# llrf_afe_fpga_bridge.net
KiCad netlist of a schematic drawn in Altium Designer
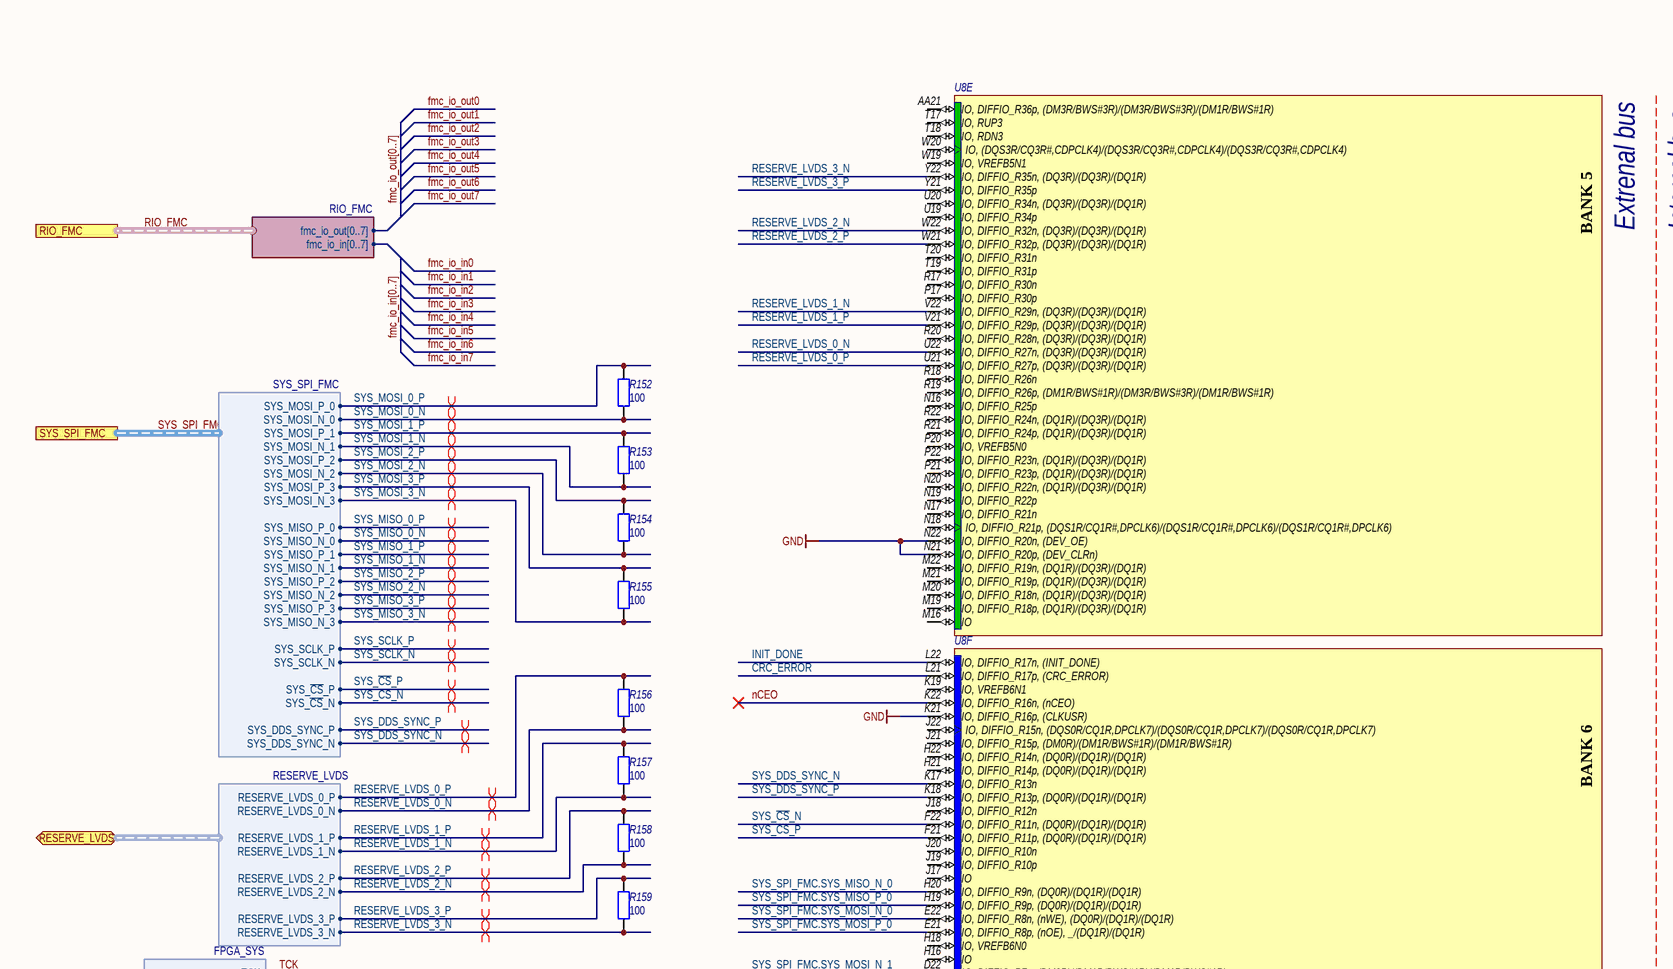
[diagram p0: llrf_afe_fpga_bridge.SchDoc, top left]
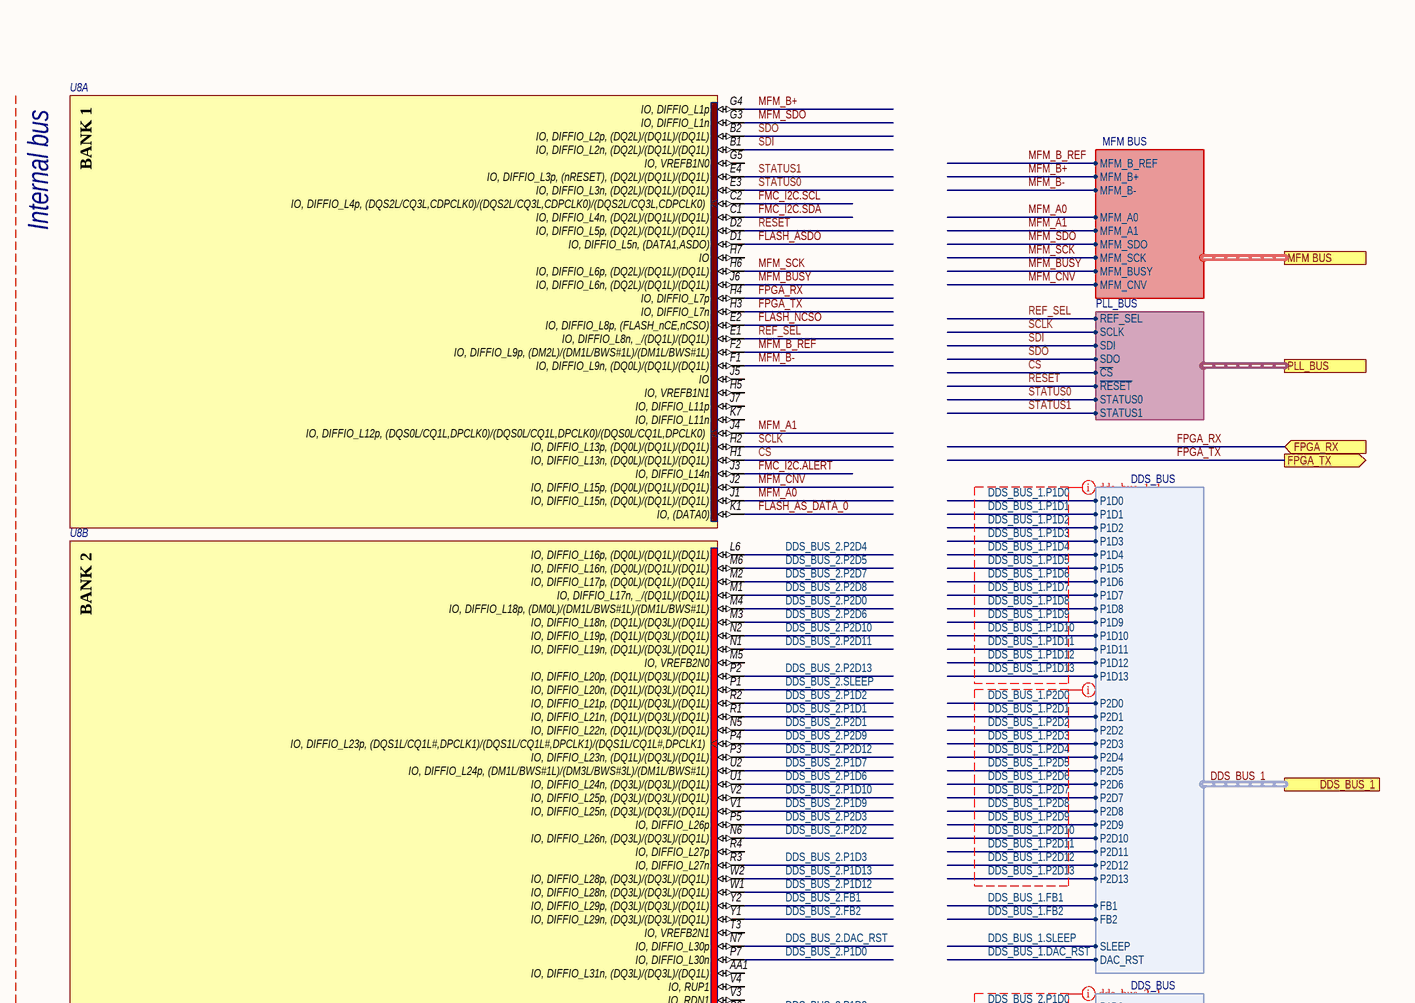
[diagram p1: llrf_afe_fpga_bridge.SchDoc, top right]
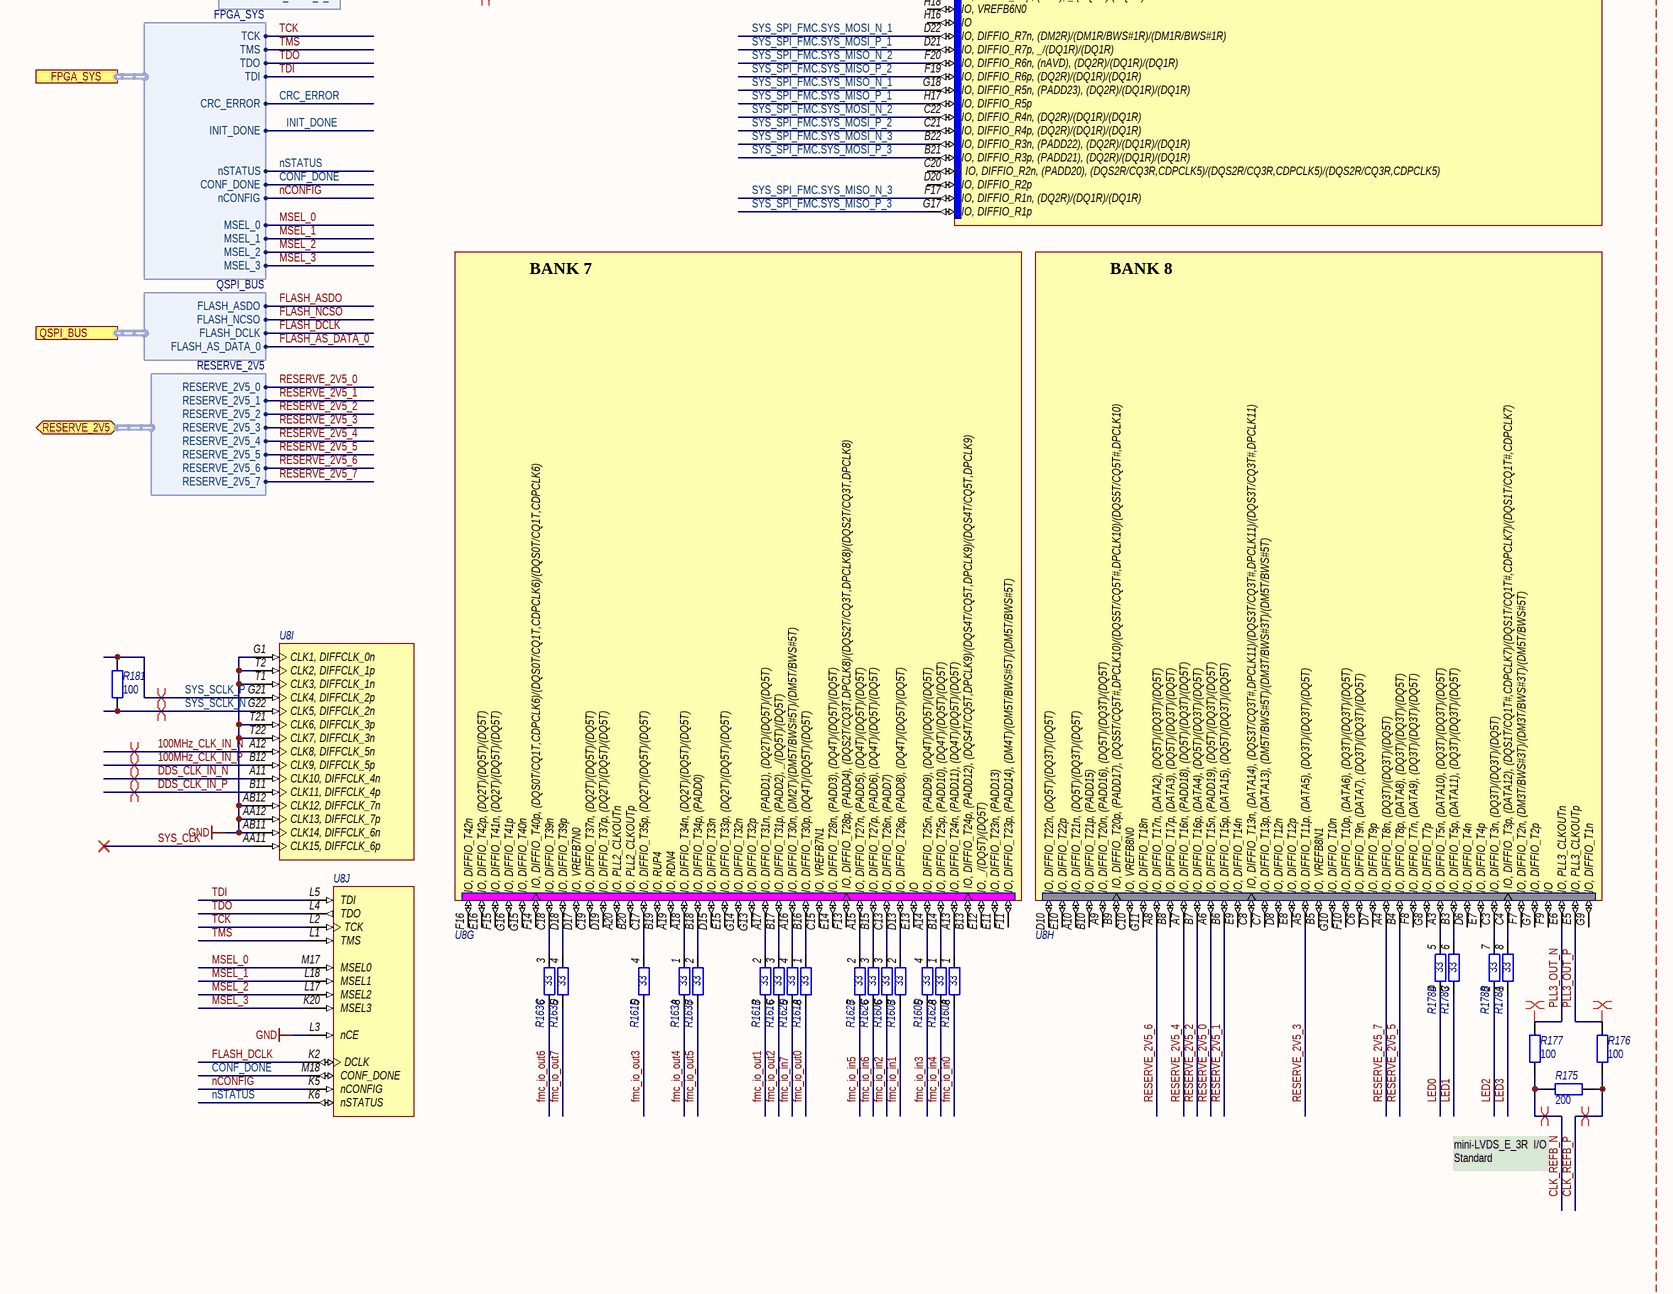
[diagram p2: llrf_afe_fpga_bridge.SchDoc, bottom left]
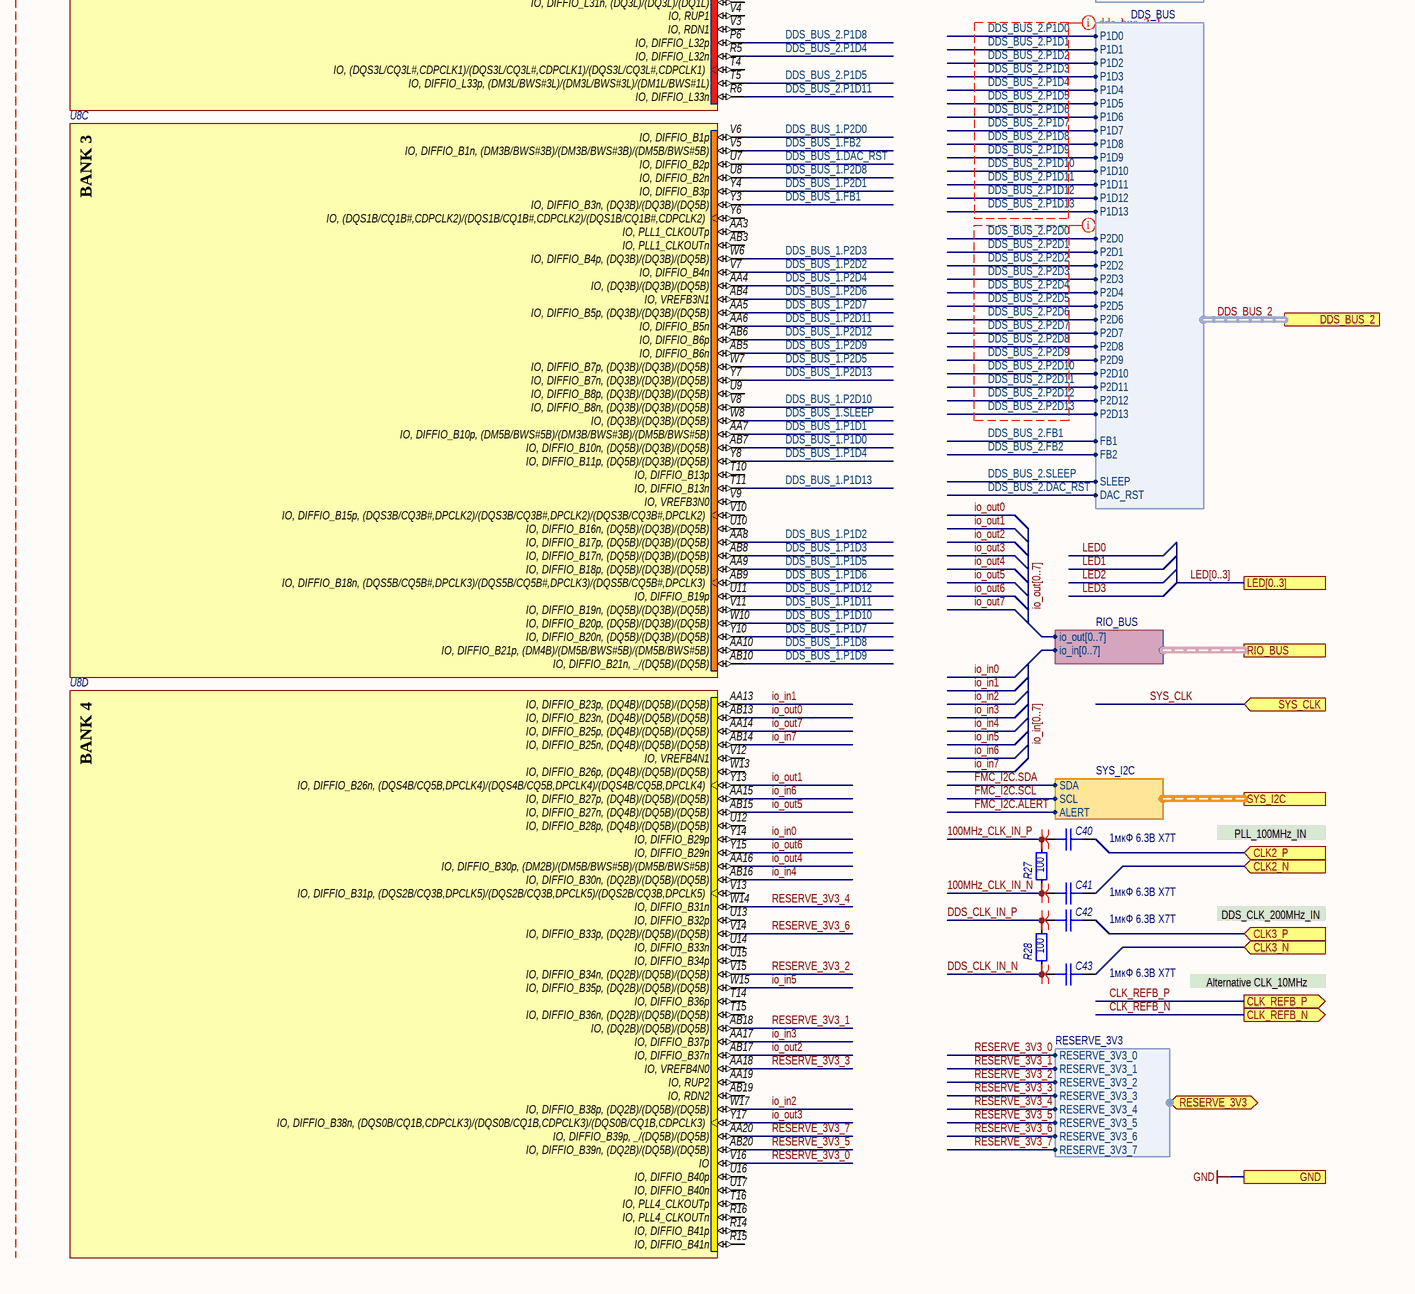
[diagram p3: llrf_afe_fpga_bridge.SchDoc, bottom right]

(export (version "E")
  (design (tool "Eeschema 10.0.6"))
  (components
    (comp (ref "C40")
      (value "1мкФ 6.3В X7T")
      (footprint "SMD_C0603")
      (description "Capacitor")
      (libsource (lib "Passive") (part "Capacitor"))
    )
    (comp (ref "C41")
      (value "1мкФ 6.3В X7T")
      (footprint "SMD_C0603")
      (description "Capacitor")
      (libsource (lib "Passive") (part "Capacitor"))
    )
    (comp (ref "C42")
      (value "1мкФ 6.3В X7T")
      (footprint "SMD_C0603")
      (description "Capacitor")
      (libsource (lib "Passive") (part "Capacitor"))
    )
    (comp (ref "C43")
      (value "1мкФ 6.3В X7T")
      (footprint "SMD_C0603")
      (description "Capacitor")
      (libsource (lib "Passive") (part "Capacitor"))
    )
    (comp (ref "R27")
      (value "100")
      (footprint "SMD_0603")
      (description "Resistor")
      (libsource (lib "") (part "Resistor_1"))
    )
    (comp (ref "R28")
      (value "100")
      (footprint "SMD_0603")
      (description "Resistor")
      (libsource (lib "") (part "Resistor_1"))
    )
    (comp (ref "R152")
      (value "100")
      (footprint "SMD_0603")
      (description "Resistor")
      (libsource (lib "Passive") (part "Resistor"))
    )
    (comp (ref "R153")
      (value "100")
      (footprint "SMD_0603")
      (description "Resistor")
      (libsource (lib "Passive") (part "Resistor"))
    )
    (comp (ref "R154")
      (value "100")
      (footprint "SMD_0603")
      (description "Resistor")
      (libsource (lib "Passive") (part "Resistor"))
    )
    (comp (ref "R155")
      (value "100")
      (footprint "SMD_0603")
      (description "Resistor")
      (libsource (lib "Passive") (part "Resistor"))
    )
    (comp (ref "R156")
      (value "100")
      (footprint "SMD_0603")
      (description "Resistor")
      (libsource (lib "Passive") (part "Resistor"))
    )
    (comp (ref "R157")
      (value "100")
      (footprint "SMD_0603")
      (description "Resistor")
      (libsource (lib "Passive") (part "Resistor"))
    )
    (comp (ref "R158")
      (value "100")
      (footprint "SMD_0603")
      (description "Resistor")
      (libsource (lib "Passive") (part "Resistor"))
    )
    (comp (ref "R159")
      (value "100")
      (footprint "SMD_0603")
      (description "Resistor")
      (libsource (lib "Passive") (part "Resistor"))
    )
    (comp (ref "R160")
      (value "33")
      (footprint "TC124")
      (description "4 Chip Resistor Array")
      (libsource (lib "") (part "Resistor-4_1"))
    )
    (comp (ref "R161")
      (value "33")
      (footprint "TC124")
      (description "4 Chip Resistor Array")
      (libsource (lib "") (part "Resistor-4_1"))
    )
    (comp (ref "R162")
      (value "33")
      (footprint "TC124")
      (description "4 Chip Resistor Array")
      (libsource (lib "") (part "Resistor-4_1"))
    )
    (comp (ref "R163")
      (value "33")
      (footprint "TC124")
      (description "4 Chip Resistor Array")
      (libsource (lib "") (part "Resistor-4_1"))
    )
    (comp (ref "R175")
      (value "200")
      (footprint "SMD_0603")
      (description "Resistor")
      (libsource (lib "") (part "Resistor_2"))
    )
    (comp (ref "R176")
      (value "100")
      (footprint "SMD_0603")
      (description "Resistor")
      (libsource (lib "Passive") (part "Resistor"))
    )
    (comp (ref "R177")
      (value "100")
      (footprint "SMD_0603")
      (description "Resistor")
      (libsource (lib "Passive") (part "Resistor"))
    )
    (comp (ref "R178")
      (value "33")
      (footprint "TC124")
      (description "4 Chip Resistor Array")
      (libsource (lib "Passive") (part "Resistor-4"))
    )
    (comp (ref "R181")
      (value "100")
      (footprint "SMD_0603")
      (description "Resistor")
      (libsource (lib "Passive") (part "Resistor"))
    )
    (comp (ref "U8")
      (value "EP4CE55F23C8")
      (footprint "FBGA484_A-240")
      (fields (field (name "MANUFACTURER") "Altera"))
      (libsource (lib "Altium Content Vault") (part "FPGA-ALEP4C-EP4CE55-F484"))
    )
  )
  (nets
    (net (code "15") (name "/100MHz_CLK_IN_N") (class "Default")
      (node (ref "C41") (pin "1") (pinfunction "1_1") (pintype "passive"))
      (node (ref "R27") (pin "1") (pinfunction "1_1") (pintype "passive"))
      (node (ref "U8") (pin "A12") (pinfunction "CLK8,_DIFFCLK_5n_A12") (pintype "input"))
    )
    (net (code "16") (name "/100MHz_CLK_IN_P") (class "Default")
      (node (ref "C40") (pin "2") (pinfunction "2_2") (pintype "passive"))
      (node (ref "R27") (pin "2") (pinfunction "2_2") (pintype "passive"))
      (node (ref "U8") (pin "B12") (pinfunction "CLK9,_DIFFCLK_5p_B12") (pintype "input"))
    )
    (net (code "17") (name "/CLK2_N") (class "Default")
      (node (ref "C41") (pin "2") (pinfunction "2_2") (pintype "passive"))
    )
    (net (code "18") (name "/CLK2_P") (class "Default")
      (node (ref "C40") (pin "1") (pinfunction "1_1") (pintype "passive"))
    )
    (net (code "19") (name "/CLK3_N") (class "Default")
      (node (ref "C43") (pin "2") (pinfunction "2_2") (pintype "passive"))
    )
    (net (code "20") (name "/CLK3_P") (class "Default")
      (node (ref "C42") (pin "1") (pinfunction "1_1") (pintype "passive"))
    )
    (net (code "21") (name "/CLK_REFB_N") (class "Default")
      (node (ref "R175") (pin "2") (pinfunction "2_2") (pintype "passive"))
      (node (ref "R177") (pin "2") (pinfunction "2_2") (pintype "passive"))
    )
    (net (code "22") (name "/CLK_REFB_P") (class "Default")
      (node (ref "R175") (pin "1") (pinfunction "1_1") (pintype "passive"))
      (node (ref "R176") (pin "2") (pinfunction "2_2") (pintype "passive"))
    )
    (net (code "23") (name "/CONF_DONE") (class "Default")
      (node (ref "U8") (pin "M18") (pinfunction "CONF_DONE_M18") (pintype "bidirectional"))
    )
    (net (code "24") (name "/CRC_ERROR") (class "Default")
      (node (ref "U8") (pin "L21") (pinfunction "IO,_DIFFIO_R17p,_(CRC_ERROR)_L21") (pintype "bidirectional"))
    )
    (net (code "25") (name "/DDS_BUS_1.DAC_RST") (class "Default")
      (node (ref "U8") (pin "U7") (pinfunction "IO,_DIFFIO_B2p_U7") (pintype "bidirectional"))
    )
    (net (code "26") (name "/DDS_BUS_1.FB1") (class "Default")
      (node (ref "U8") (pin "Y3") (pinfunction "IO,_DIFFIO_B3n,_(DQ3B)/(DQ3B)/(DQ5B)_Y3") (pintype "bidirectional"))
    )
    (net (code "27") (name "/DDS_BUS_1.FB2") (class "Default")
      (node (ref "U8") (pin "V5") (pinfunction "IO,_DIFFIO_B1n,_(DM3B/BWS#3B)/(DM3B/BWS#3B)/(DM5B/BWS#5B)_V5") (pintype "bidirectional"))
    )
    (net (code "28") (name "/DDS_BUS_1.P1D0") (class "Default")
      (node (ref "U8") (pin "AB7") (pinfunction "IO,_DIFFIO_B10n,_(DQ5B)/(DQ3B)/(DQ5B)_AB7") (pintype "bidirectional"))
    )
    (net (code "29") (name "/DDS_BUS_1.P1D1") (class "Default")
      (node (ref "U8") (pin "AA7") (pinfunction "IO,_DIFFIO_B10p,_(DM5B/BWS#5B)/(DM3B/BWS#3B)/(DM5B/BWS#5B)_AA7") (pintype "bidirectional"))
    )
    (net (code "30") (name "/DDS_BUS_1.P1D2") (class "Default")
      (node (ref "U8") (pin "AA8") (pinfunction "IO,_DIFFIO_B17p,_(DQ5B)/(DQ3B)/(DQ5B)_AA8") (pintype "bidirectional"))
    )
    (net (code "31") (name "/DDS_BUS_1.P1D3") (class "Default")
      (node (ref "U8") (pin "AB8") (pinfunction "IO,_DIFFIO_B17n,_(DQ5B)/(DQ3B)/(DQ5B)_AB8") (pintype "bidirectional"))
    )
    (net (code "32") (name "/DDS_BUS_1.P1D4") (class "Default")
      (node (ref "U8") (pin "Y8") (pinfunction "IO,_DIFFIO_B11p,_(DQ5B)/(DQ3B)/(DQ5B)_Y8") (pintype "bidirectional"))
    )
    (net (code "33") (name "/DDS_BUS_1.P1D5") (class "Default")
      (node (ref "U8") (pin "AA9") (pinfunction "IO,_DIFFIO_B18p,_(DQ5B)/(DQ3B)/(DQ5B)_AA9") (pintype "bidirectional"))
    )
    (net (code "34") (name "/DDS_BUS_1.P1D6") (class "Default")
      (node (ref "U8") (pin "AB9") (pinfunction "IO,_DIFFIO_B18n,_(DQS5B/CQ5B#,DPCLK3)/(DQS5B/CQ5B#,DPCLK3)/(DQS5B/CQ5B#,DPCLK3)_AB9") (pintype "bidirectional"))
    )
    (net (code "35") (name "/DDS_BUS_1.P1D7") (class "Default")
      (node (ref "U8") (pin "Y10") (pinfunction "IO,_DIFFIO_B20n,_(DQ5B)/(DQ3B)/(DQ5B)_Y10") (pintype "bidirectional"))
    )
    (net (code "36") (name "/DDS_BUS_1.P1D8") (class "Default")
      (node (ref "U8") (pin "AA10") (pinfunction "IO,_DIFFIO_B21p,_(DM4B)/(DM5B/BWS#5B)/(DM5B/BWS#5B)_AA10") (pintype "bidirectional"))
    )
    (net (code "37") (name "/DDS_BUS_1.P1D9") (class "Default")
      (node (ref "U8") (pin "AB10") (pinfunction "IO,_DIFFIO_B21n,__/(DQ5B)/(DQ5B)_AB10") (pintype "bidirectional"))
    )
    (net (code "38") (name "/DDS_BUS_1.P1D10") (class "Default")
      (node (ref "U8") (pin "W10") (pinfunction "IO,_DIFFIO_B20p,_(DQ5B)/(DQ3B)/(DQ5B)_W10") (pintype "bidirectional"))
    )
    (net (code "39") (name "/DDS_BUS_1.P1D11") (class "Default")
      (node (ref "U8") (pin "V11") (pinfunction "IO,_DIFFIO_B19n,_(DQ5B)/(DQ3B)/(DQ5B)_V11") (pintype "bidirectional"))
    )
    (net (code "40") (name "/DDS_BUS_1.P1D12") (class "Default")
      (node (ref "U8") (pin "U11") (pinfunction "IO,_DIFFIO_B19p_U11") (pintype "bidirectional"))
    )
    (net (code "41") (name "/DDS_BUS_1.P1D13") (class "Default")
      (node (ref "U8") (pin "T11") (pinfunction "IO,_DIFFIO_B13n_T11") (pintype "bidirectional"))
    )
    (net (code "42") (name "/DDS_BUS_1.P2D0") (class "Default")
      (node (ref "U8") (pin "V6") (pinfunction "IO,_DIFFIO_B1p_V6") (pintype "bidirectional"))
    )
    (net (code "43") (name "/DDS_BUS_1.P2D1") (class "Default")
      (node (ref "U8") (pin "Y4") (pinfunction "IO,_DIFFIO_B3p_Y4") (pintype "bidirectional"))
    )
    (net (code "44") (name "/DDS_BUS_1.P2D2") (class "Default")
      (node (ref "U8") (pin "V7") (pinfunction "IO,_DIFFIO_B4n_V7") (pintype "bidirectional"))
    )
    (net (code "45") (name "/DDS_BUS_1.P2D3") (class "Default")
      (node (ref "U8") (pin "W6") (pinfunction "IO,_DIFFIO_B4p,_(DQ3B)/(DQ3B)/(DQ5B)_W6") (pintype "bidirectional"))
    )
    (net (code "46") (name "/DDS_BUS_1.P2D4") (class "Default")
      (node (ref "U8") (pin "AA4") (pinfunction "IO,_(DQ3B)/(DQ3B)/(DQ5B)_AA4") (pintype "bidirectional"))
    )
    (net (code "47") (name "/DDS_BUS_1.P2D5") (class "Default")
      (node (ref "U8") (pin "W7") (pinfunction "IO,_DIFFIO_B7p,_(DQ3B)/(DQ3B)/(DQ5B)_W7") (pintype "bidirectional"))
    )
    (net (code "48") (name "/DDS_BUS_1.P2D6") (class "Default")
      (node (ref "U8") (pin "AB4") (pinfunction "IO,_VREFB3N1_AB4") (pintype "bidirectional"))
    )
    (net (code "49") (name "/DDS_BUS_1.P2D7") (class "Default")
      (node (ref "U8") (pin "AA5") (pinfunction "IO,_DIFFIO_B5p,_(DQ3B)/(DQ3B)/(DQ5B)_AA5") (pintype "bidirectional"))
    )
    (net (code "50") (name "/DDS_BUS_1.P2D8") (class "Default")
      (node (ref "U8") (pin "U8") (pinfunction "IO,_DIFFIO_B2n_U8") (pintype "bidirectional"))
    )
    (net (code "51") (name "/DDS_BUS_1.P2D9") (class "Default")
      (node (ref "U8") (pin "AB5") (pinfunction "IO,_DIFFIO_B6n_AB5") (pintype "bidirectional"))
    )
    (net (code "52") (name "/DDS_BUS_1.P2D10") (class "Default")
      (node (ref "U8") (pin "V8") (pinfunction "IO,_DIFFIO_B8n,_(DQ3B)/(DQ3B)/(DQ5B)_V8") (pintype "bidirectional"))
    )
    (net (code "53") (name "/DDS_BUS_1.P2D11") (class "Default")
      (node (ref "U8") (pin "AA6") (pinfunction "IO,_DIFFIO_B5n_AA6") (pintype "bidirectional"))
    )
    (net (code "54") (name "/DDS_BUS_1.P2D12") (class "Default")
      (node (ref "U8") (pin "AB6") (pinfunction "IO,_DIFFIO_B6p_AB6") (pintype "bidirectional"))
    )
    (net (code "55") (name "/DDS_BUS_1.P2D13") (class "Default")
      (node (ref "U8") (pin "Y7") (pinfunction "IO,_DIFFIO_B7n,_(DQ3B)/(DQ3B)/(DQ5B)_Y7") (pintype "bidirectional"))
    )
    (net (code "56") (name "/DDS_BUS_1.SLEEP") (class "Default")
      (node (ref "U8") (pin "W8") (pinfunction "IO,_(DQ3B)/(DQ3B)/(DQ5B)_W8") (pintype "bidirectional"))
    )
    (net (code "58") (name "/DDS_BUS_2.DAC_RST") (class "Default")
      (node (ref "U8") (pin "N7") (pinfunction "IO,_DIFFIO_L30p_N7") (pintype "bidirectional"))
    )
    (net (code "59") (name "/DDS_BUS_2.FB1") (class "Default")
      (node (ref "U8") (pin "Y2") (pinfunction "IO,_DIFFIO_L29p,_(DQ3L)/(DQ3L)/(DQ1L)_Y2") (pintype "bidirectional"))
    )
    (net (code "60") (name "/DDS_BUS_2.FB2") (class "Default")
      (node (ref "U8") (pin "Y1") (pinfunction "IO,_DIFFIO_L29n,_(DQ3L)/(DQ3L)/(DQ1L)_Y1") (pintype "bidirectional"))
    )
    (net (code "61") (name "/DDS_BUS_2.P1D0") (class "Default")
      (node (ref "U8") (pin "P7") (pinfunction "IO,_DIFFIO_L30n_P7") (pintype "bidirectional"))
    )
    (net (code "62") (name "/DDS_BUS_2.P1D1") (class "Default")
      (node (ref "U8") (pin "R1") (pinfunction "IO,_DIFFIO_L21n,_(DQ1L)/(DQ3L)/(DQ1L)_R1") (pintype "bidirectional"))
    )
    (net (code "63") (name "/DDS_BUS_2.P1D2") (class "Default")
      (node (ref "U8") (pin "R2") (pinfunction "IO,_DIFFIO_L21p,_(DQ1L)/(DQ3L)/(DQ1L)_R2") (pintype "bidirectional"))
    )
    (net (code "64") (name "/DDS_BUS_2.P1D3") (class "Default")
      (node (ref "U8") (pin "R3") (pinfunction "IO,_DIFFIO_L27n_R3") (pintype "bidirectional"))
    )
    (net (code "65") (name "/DDS_BUS_2.P1D4") (class "Default")
      (node (ref "U8") (pin "R5") (pinfunction "IO,_DIFFIO_L32n_R5") (pintype "bidirectional"))
    )
    (net (code "66") (name "/DDS_BUS_2.P1D5") (class "Default")
      (node (ref "U8") (pin "T5") (pinfunction "IO,_DIFFIO_L33p,_(DM3L/BWS#3L)/(DM3L/BWS#3L)/(DM1L/BWS#1L)_T5") (pintype "bidirectional"))
    )
    (net (code "67") (name "/DDS_BUS_2.P1D6") (class "Default")
      (node (ref "U8") (pin "U1") (pinfunction "IO,_DIFFIO_L24n,_(DQ3L)/(DQ3L)/(DQ1L)_U1") (pintype "bidirectional"))
    )
    (net (code "68") (name "/DDS_BUS_2.P1D7") (class "Default")
      (node (ref "U8") (pin "U2") (pinfunction "IO,_DIFFIO_L24p,_(DM1L/BWS#1L)/(DM3L/BWS#3L)/(DM1L/BWS#1L)_U2") (pintype "bidirectional"))
    )
    (net (code "69") (name "/DDS_BUS_2.P1D8") (class "Default")
      (node (ref "U8") (pin "P6") (pinfunction "IO,_DIFFIO_L32p_P6") (pintype "bidirectional"))
    )
    (net (code "70") (name "/DDS_BUS_2.P1D9") (class "Default")
      (node (ref "U8") (pin "V1") (pinfunction "IO,_DIFFIO_L25n,_(DQ3L)/(DQ3L)/(DQ1L)_V1") (pintype "bidirectional"))
    )
    (net (code "71") (name "/DDS_BUS_2.P1D10") (class "Default")
      (node (ref "U8") (pin "V2") (pinfunction "IO,_DIFFIO_L25p,_(DQ3L)/(DQ3L)/(DQ1L)_V2") (pintype "bidirectional"))
    )
    (net (code "72") (name "/DDS_BUS_2.P1D11") (class "Default")
      (node (ref "U8") (pin "R6") (pinfunction "IO,_DIFFIO_L33n_R6") (pintype "bidirectional"))
    )
    (net (code "73") (name "/DDS_BUS_2.P1D12") (class "Default")
      (node (ref "U8") (pin "W1") (pinfunction "IO,_DIFFIO_L28n,_(DQ3L)/(DQ3L)/(DQ1L)_W1") (pintype "bidirectional"))
    )
    (net (code "74") (name "/DDS_BUS_2.P1D13") (class "Default")
      (node (ref "U8") (pin "W2") (pinfunction "IO,_DIFFIO_L28p,_(DQ3L)/(DQ3L)/(DQ1L)_W2") (pintype "bidirectional"))
    )
    (net (code "75") (name "/DDS_BUS_2.P2D0") (class "Default")
      (node (ref "U8") (pin "M4") (pinfunction "IO,_DIFFIO_L18p,_(DM0L)/(DM1L/BWS#1L)/(DM1L/BWS#1L)_M4") (pintype "bidirectional"))
    )
    (net (code "76") (name "/DDS_BUS_2.P2D1") (class "Default")
      (node (ref "U8") (pin "N5") (pinfunction "IO,_DIFFIO_L22n,_(DQ1L)/(DQ3L)/(DQ1L)_N5") (pintype "bidirectional"))
    )
    (net (code "77") (name "/DDS_BUS_2.P2D2") (class "Default")
      (node (ref "U8") (pin "N6") (pinfunction "IO,_DIFFIO_L26n,_(DQ3L)/(DQ3L)/(DQ1L)_N6") (pintype "bidirectional"))
    )
    (net (code "78") (name "/DDS_BUS_2.P2D3") (class "Default")
      (node (ref "U8") (pin "P5") (pinfunction "IO,_DIFFIO_L26p_P5") (pintype "bidirectional"))
    )
    (net (code "79") (name "/DDS_BUS_2.P2D4") (class "Default")
      (node (ref "U8") (pin "L6") (pinfunction "IO,_DIFFIO_L16p,_(DQ0L)/(DQ1L)/(DQ1L)_L6") (pintype "bidirectional"))
    )
    (net (code "80") (name "/DDS_BUS_2.P2D5") (class "Default")
      (node (ref "U8") (pin "M6") (pinfunction "IO,_DIFFIO_L16n,_(DQ0L)/(DQ1L)/(DQ1L)_M6") (pintype "bidirectional"))
    )
    (net (code "81") (name "/DDS_BUS_2.P2D6") (class "Default")
      (node (ref "U8") (pin "M3") (pinfunction "IO,_DIFFIO_L18n,_(DQ1L)/(DQ3L)/(DQ1L)_M3") (pintype "bidirectional"))
    )
    (net (code "82") (name "/DDS_BUS_2.P2D7") (class "Default")
      (node (ref "U8") (pin "M2") (pinfunction "IO,_DIFFIO_L17p,_(DQ0L)/(DQ1L)/(DQ1L)_M2") (pintype "bidirectional"))
    )
    (net (code "83") (name "/DDS_BUS_2.P2D8") (class "Default")
      (node (ref "U8") (pin "M1") (pinfunction "IO,_DIFFIO_L17n,__/(DQ1L)/(DQ1L)_M1") (pintype "bidirectional"))
    )
    (net (code "84") (name "/DDS_BUS_2.P2D9") (class "Default")
      (node (ref "U8") (pin "P4") (pinfunction "IO,_DIFFIO_L23p,_(DQS1L/CQ1L#,DPCLK1)/(DQS1L/CQ1L#,DPCLK1)/(DQS1L/CQ1L#,DPCLK1)_P4") (pintype "bidirectional"))
    )
    (net (code "85") (name "/DDS_BUS_2.P2D10") (class "Default")
      (node (ref "U8") (pin "N2") (pinfunction "IO,_DIFFIO_L19p,_(DQ1L)/(DQ3L)/(DQ1L)_N2") (pintype "bidirectional"))
    )
    (net (code "86") (name "/DDS_BUS_2.P2D11") (class "Default")
      (node (ref "U8") (pin "N1") (pinfunction "IO,_DIFFIO_L19n,_(DQ1L)/(DQ3L)/(DQ1L)_N1") (pintype "bidirectional"))
    )
    (net (code "87") (name "/DDS_BUS_2.P2D12") (class "Default")
      (node (ref "U8") (pin "P3") (pinfunction "IO,_DIFFIO_L23n,_(DQ1L)/(DQ3L)/(DQ1L)_P3") (pintype "bidirectional"))
    )
    (net (code "88") (name "/DDS_BUS_2.P2D13") (class "Default")
      (node (ref "U8") (pin "P2") (pinfunction "IO,_DIFFIO_L20p,_(DQ1L)/(DQ3L)/(DQ1L)_P2") (pintype "bidirectional"))
    )
    (net (code "89") (name "/DDS_BUS_2.SLEEP") (class "Default")
      (node (ref "U8") (pin "P1") (pinfunction "IO,_DIFFIO_L20n,_(DQ1L)/(DQ3L)/(DQ1L)_P1") (pintype "bidirectional"))
    )
    (net (code "91") (name "/DDS_CLK_IN_N") (class "Default")
      (node (ref "C43") (pin "1") (pinfunction "1_1") (pintype "passive"))
      (node (ref "R28") (pin "1") (pinfunction "1_1") (pintype "passive"))
      (node (ref "U8") (pin "A11") (pinfunction "CLK10,_DIFFCLK_4n_A11") (pintype "input"))
    )
    (net (code "92") (name "/DDS_CLK_IN_P") (class "Default")
      (node (ref "C42") (pin "2") (pinfunction "2_2") (pintype "passive"))
      (node (ref "R28") (pin "2") (pinfunction "2_2") (pintype "passive"))
      (node (ref "U8") (pin "B11") (pinfunction "CLK11,_DIFFCLK_4p_B11") (pintype "input"))
    )
    (net (code "93") (name "/FLASH_ASDO") (class "Default")
      (node (ref "U8") (pin "D1") (pinfunction "IO,_DIFFIO_L5n,_(DATA1,ASDO)_D1") (pintype "bidirectional"))
    )
    (net (code "94") (name "/FLASH_AS_DATA_0") (class "Default")
      (node (ref "U8") (pin "K1") (pinfunction "IO,_(DATA0)_K1") (pintype "bidirectional"))
    )
    (net (code "95") (name "/FLASH_DCLK") (class "Default")
      (node (ref "U8") (pin "K2") (pinfunction "DCLK_K2") (pintype "bidirectional"))
    )
    (net (code "96") (name "/FLASH_NCSO") (class "Default")
      (node (ref "U8") (pin "E2") (pinfunction "IO,_DIFFIO_L8p,_(FLASH_nCE,nCSO)_E2") (pintype "bidirectional"))
    )
    (net (code "97") (name "/FMC_I2C.ALERT") (class "Default")
      (node (ref "U8") (pin "J3") (pinfunction "IO,_DIFFIO_L14n_J3") (pintype "bidirectional"))
    )
    (net (code "98") (name "/FMC_I2C.SCL") (class "Default")
      (node (ref "U8") (pin "C2") (pinfunction "IO,_DIFFIO_L4p,_(DQS2L/CQ3L,CDPCLK0)/(DQS2L/CQ3L,CDPCLK0)/(DQS2L/CQ3L,CDPCLK0)_C2") (pintype "bidirectional"))
    )
    (net (code "99") (name "/FMC_I2C.SDA") (class "Default")
      (node (ref "U8") (pin "C1") (pinfunction "IO,_DIFFIO_L4n,_(DQ2L)/(DQ1L)/(DQ1L)_C1") (pintype "bidirectional"))
    )
    (net (code "100") (name "/FPGA_RX") (class "Default")
      (node (ref "U8") (pin "H4") (pinfunction "IO,_DIFFIO_L7p_H4") (pintype "bidirectional"))
    )
    (net (code "101") (name "/FPGA_TX") (class "Default")
      (node (ref "U8") (pin "H3") (pinfunction "IO,_DIFFIO_L7n_H3") (pintype "bidirectional"))
    )
    (net (code "102") (name "/INIT_DONE") (class "Default")
      (node (ref "U8") (pin "L22") (pinfunction "IO,_DIFFIO_R17n,_(INIT_DONE)_L22") (pintype "bidirectional"))
    )
    (net (code "103") (name "/LED0") (class "Default")
      (node (ref "R178") (pin "4") (pinfunction "4_4") (pintype "passive"))
    )
    (net (code "104") (name "/LED1") (class "Default")
      (node (ref "R178") (pin "3") (pinfunction "3_3") (pintype "passive"))
    )
    (net (code "105") (name "/LED2") (class "Default")
      (node (ref "R178") (pin "2") (pinfunction "2_2") (pintype "passive"))
    )
    (net (code "106") (name "/LED3") (class "Default")
      (node (ref "R178") (pin "1") (pinfunction "1_1") (pintype "passive"))
    )
    (net (code "108") (name "/MFM_A0") (class "Default")
      (node (ref "U8") (pin "J1") (pinfunction "IO,_DIFFIO_L15n,_(DQ0L)/(DQ1L)/(DQ1L)_J1") (pintype "bidirectional"))
    )
    (net (code "109") (name "/MFM_A1") (class "Default")
      (node (ref "U8") (pin "J4") (pinfunction "IO,_DIFFIO_L12p,_(DQS0L/CQ1L,DPCLK0)/(DQS0L/CQ1L,DPCLK0)/(DQS0L/CQ1L,DPCLK0)_J4") (pintype "bidirectional"))
    )
    (net (code "110") (name "/MFM_B+") (class "Default")
      (node (ref "U8") (pin "G4") (pinfunction "IO,_DIFFIO_L1p_G4") (pintype "bidirectional"))
    )
    (net (code "111") (name "/MFM_B-") (class "Default")
      (node (ref "U8") (pin "F1") (pinfunction "IO,_DIFFIO_L9n,_(DQ0L)/(DQ1L)/(DQ1L)_F1") (pintype "bidirectional"))
    )
    (net (code "112") (name "/MFM_BUSY") (class "Default")
      (node (ref "U8") (pin "J6") (pinfunction "IO,_DIFFIO_L6n,_(DQ2L)/(DQ1L)/(DQ1L)_J6") (pintype "bidirectional"))
    )
    (net (code "113") (name "/MFM_B_REF") (class "Default")
      (node (ref "U8") (pin "F2") (pinfunction "IO,_DIFFIO_L9p,_(DM2L)/(DM1L/BWS#1L)/(DM1L/BWS#1L)_F2") (pintype "bidirectional"))
    )
    (net (code "114") (name "/MFM_CNV") (class "Default")
      (node (ref "U8") (pin "J2") (pinfunction "IO,_DIFFIO_L15p,_(DQ0L)/(DQ1L)/(DQ1L)_J2") (pintype "bidirectional"))
    )
    (net (code "115") (name "/MFM_SCK") (class "Default")
      (node (ref "U8") (pin "H6") (pinfunction "IO,_DIFFIO_L6p,_(DQ2L)/(DQ1L)/(DQ1L)_H6") (pintype "bidirectional"))
    )
    (net (code "116") (name "/MFM_SDO") (class "Default")
      (node (ref "U8") (pin "G3") (pinfunction "IO,_DIFFIO_L1n_G3") (pintype "bidirectional"))
    )
    (net (code "117") (name "/MSEL_0") (class "Default")
      (node (ref "U8") (pin "M17") (pinfunction "MSEL0_M17") (pintype "input"))
    )
    (net (code "118") (name "/MSEL_1") (class "Default")
      (node (ref "U8") (pin "L18") (pinfunction "MSEL1_L18") (pintype "input"))
    )
    (net (code "119") (name "/MSEL_2") (class "Default")
      (node (ref "U8") (pin "L17") (pinfunction "MSEL2_L17") (pintype "input"))
    )
    (net (code "120") (name "/MSEL_3") (class "Default")
      (node (ref "U8") (pin "K20") (pinfunction "MSEL3_K20") (pintype "input"))
    )
    (net (code "121") (name "/PLL3_OUT_N") (class "Default")
      (node (ref "R177") (pin "1") (pinfunction "1_1") (pintype "passive"))
      (node (ref "U8") (pin "E6") (pinfunction "IO,_PLL3_CLKOUTn_E6") (pintype "bidirectional"))
    )
    (net (code "122") (name "/PLL3_OUT_P") (class "Default")
      (node (ref "R176") (pin "1") (pinfunction "1_1") (pintype "passive"))
      (node (ref "U8") (pin "E5") (pinfunction "IO,_PLL3_CLKOUTp_E5") (pintype "bidirectional"))
    )
    (net (code "123") (name "/REF_SEL") (class "Default")
      (node (ref "U8") (pin "E1") (pinfunction "IO,_DIFFIO_L8n,__/(DQ1L)/(DQ1L)_E1") (pintype "bidirectional"))
    )
    (net (code "124") (name "/RESERVE_2V5_0") (class "Default")
      (node (ref "U8") (pin "A6") (pinfunction "IO,_DIFFIO_T15n,_(PADD19),_(DQ5T)/(DQ3T)/(DQ5T)_A6") (pintype "bidirectional"))
    )
    (net (code "125") (name "/RESERVE_2V5_1") (class "Default")
      (node (ref "U8") (pin "B6") (pinfunction "IO,_DIFFIO_T15p,_(DATA15),_(DQ5T)/(DQ3T)/(DQ5T)_B6") (pintype "bidirectional"))
    )
    (net (code "126") (name "/RESERVE_2V5_2") (class "Default")
      (node (ref "U8") (pin "B7") (pinfunction "IO,_DIFFIO_T16p,_(DATA4),_(DQ5T)/(DQ3T)/(DQ5T)_B7") (pintype "bidirectional"))
    )
    (net (code "127") (name "/RESERVE_2V5_3") (class "Default")
      (node (ref "U8") (pin "A5") (pinfunction "IO,_DIFFIO_T11p,_(DATA5),_(DQ3T)/(DQ3T)/(DQ5T)_A5") (pintype "bidirectional"))
    )
    (net (code "128") (name "/RESERVE_2V5_4") (class "Default")
      (node (ref "U8") (pin "A7") (pinfunction "IO,_DIFFIO_T16n,_(PADD18),_(DQ5T)/(DQ3T)/(DQ5T)_A7") (pintype "bidirectional"))
    )
    (net (code "129") (name "/RESERVE_2V5_5") (class "Default")
      (node (ref "U8") (pin "B4") (pinfunction "IO,_DIFFIO_T8p,_(DATA8),_(DQ3T)/(DQ3T)/(DQ5T)_B4") (pintype "bidirectional"))
    )
    (net (code "130") (name "/RESERVE_2V5_6") (class "Default")
      (node (ref "U8") (pin "A8") (pinfunction "IO,_DIFFIO_T17n,_(DATA2),_(DQ5T)/(DQ3T)/(DQ5T)_A8") (pintype "bidirectional"))
    )
    (net (code "131") (name "/RESERVE_2V5_7") (class "Default")
      (node (ref "U8") (pin "A4") (pinfunction "IO,_DIFFIO_T8n,_(DQ3T)/(DQ3T)/(DQ5T)_A4") (pintype "bidirectional"))
    )
    (net (code "132") (name "/RESERVE_3V3_0") (class "Default")
      (node (ref "U8") (pin "V16") (pinfunction "IO_V16") (pintype "bidirectional"))
    )
    (net (code "133") (name "/RESERVE_3V3_1") (class "Default")
      (node (ref "U8") (pin "AB18") (pinfunction "IO,_(DQ2B)/(DQ5B)/(DQ5B)_AB18") (pintype "bidirectional"))
    )
    (net (code "134") (name "/RESERVE_3V3_2") (class "Default")
      (node (ref "U8") (pin "V15") (pinfunction "IO,_DIFFIO_B34n,_(DQ2B)/(DQ5B)/(DQ5B)_V15") (pintype "bidirectional"))
    )
    (net (code "135") (name "/RESERVE_3V3_3") (class "Default")
      (node (ref "U8") (pin "AA18") (pinfunction "IO,_VREFB4N0_AA18") (pintype "bidirectional"))
    )
    (net (code "136") (name "/RESERVE_3V3_4") (class "Default")
      (node (ref "U8") (pin "W14") (pinfunction "IO,_DIFFIO_B31n_W14") (pintype "bidirectional"))
    )
    (net (code "137") (name "/RESERVE_3V3_5") (class "Default")
      (node (ref "U8") (pin "AB20") (pinfunction "IO,_DIFFIO_B39n,_(DQ2B)/(DQ5B)/(DQ5B)_AB20") (pintype "bidirectional"))
    )
    (net (code "138") (name "/RESERVE_3V3_6") (class "Default")
      (node (ref "U8") (pin "V14") (pinfunction "IO,_DIFFIO_B33p,_(DQ2B)/(DQ5B)/(DQ5B)_V14") (pintype "bidirectional"))
    )
    (net (code "139") (name "/RESERVE_3V3_7") (class "Default")
      (node (ref "U8") (pin "AA20") (pinfunction "IO,_DIFFIO_B39p,__/(DQ5B)/(DQ5B)_AA20") (pintype "bidirectional"))
    )
    (net (code "140") (name "/RESERVE_LVDS_0_N") (class "Default")
      (node (ref "R156") (pin "2") (pinfunction "2_2") (pintype "passive"))
      (node (ref "U8") (pin "U22") (pinfunction "IO,_DIFFIO_R27n,_(DQ3R)/(DQ3R)/(DQ1R)_U22") (pintype "bidirectional"))
    )
    (net (code "141") (name "/RESERVE_LVDS_0_P") (class "Default")
      (node (ref "R156") (pin "1") (pinfunction "1_1") (pintype "passive"))
      (node (ref "U8") (pin "U21") (pinfunction "IO,_DIFFIO_R27p,_(DQ3R)/(DQ3R)/(DQ1R)_U21") (pintype "bidirectional"))
    )
    (net (code "142") (name "/RESERVE_LVDS_1_N") (class "Default")
      (node (ref "R157") (pin "2") (pinfunction "2_2") (pintype "passive"))
      (node (ref "U8") (pin "V22") (pinfunction "IO,_DIFFIO_R29n,_(DQ3R)/(DQ3R)/(DQ1R)_V22") (pintype "bidirectional"))
    )
    (net (code "143") (name "/RESERVE_LVDS_1_P") (class "Default")
      (node (ref "R157") (pin "1") (pinfunction "1_1") (pintype "passive"))
      (node (ref "U8") (pin "V21") (pinfunction "IO,_DIFFIO_R29p,_(DQ3R)/(DQ3R)/(DQ1R)_V21") (pintype "bidirectional"))
    )
    (net (code "144") (name "/RESERVE_LVDS_2_N") (class "Default")
      (node (ref "R158") (pin "2") (pinfunction "2_2") (pintype "passive"))
      (node (ref "U8") (pin "W22") (pinfunction "IO,_DIFFIO_R32n,_(DQ3R)/(DQ3R)/(DQ1R)_W22") (pintype "bidirectional"))
    )
    (net (code "145") (name "/RESERVE_LVDS_2_P") (class "Default")
      (node (ref "R158") (pin "1") (pinfunction "1_1") (pintype "passive"))
      (node (ref "U8") (pin "W21") (pinfunction "IO,_DIFFIO_R32p,_(DQ3R)/(DQ3R)/(DQ1R)_W21") (pintype "bidirectional"))
    )
    (net (code "146") (name "/RESERVE_LVDS_3_N") (class "Default")
      (node (ref "R159") (pin "2") (pinfunction "2_2") (pintype "passive"))
      (node (ref "U8") (pin "Y22") (pinfunction "IO,_DIFFIO_R35n,_(DQ3R)/(DQ3R)/(DQ1R)_Y22") (pintype "bidirectional"))
    )
    (net (code "147") (name "/RESERVE_LVDS_3_P") (class "Default")
      (node (ref "R159") (pin "1") (pinfunction "1_1") (pintype "passive"))
      (node (ref "U8") (pin "Y21") (pinfunction "IO,_DIFFIO_R35p_Y21") (pintype "bidirectional"))
    )
    (net (code "149") (name "/SCLK") (class "Default")
      (node (ref "U8") (pin "H2") (pinfunction "IO,_DIFFIO_L13p,_(DQ0L)/(DQ1L)/(DQ1L)_H2") (pintype "bidirectional"))
    )
    (net (code "150") (name "/SDI") (class "Default")
      (node (ref "U8") (pin "B1") (pinfunction "IO,_DIFFIO_L2n,_(DQ2L)/(DQ1L)/(DQ1L)_B1") (pintype "bidirectional"))
    )
    (net (code "151") (name "/SDO") (class "Default")
      (node (ref "U8") (pin "B2") (pinfunction "IO,_DIFFIO_L2p,_(DQ2L)/(DQ1L)/(DQ1L)_B2") (pintype "bidirectional"))
    )
    (net (code "152") (name "/STATUS0") (class "Default")
      (node (ref "U8") (pin "E3") (pinfunction "IO,_DIFFIO_L3n,_(DQ2L)/(DQ1L)/(DQ1L)_E3") (pintype "bidirectional"))
    )
    (net (code "153") (name "/STATUS1") (class "Default")
      (node (ref "U8") (pin "E4") (pinfunction "IO,_DIFFIO_L3p,_(nRESET),_(DQ2L)/(DQ1L)/(DQ1L)_E4") (pintype "bidirectional"))
    )
    (net (code "154") (name "/SYS_CLK") (class "Default")
      (node (ref "U8") (pin "AA11") (pinfunction "CLK15,_DIFFCLK_6p_AA11") (pintype "input+no_connect"))
    )
    (net (code "155") (name "/SYS_DDS_SYNC_N") (class "Default")
      (node (ref "U8") (pin "K17") (pinfunction "IO,_DIFFIO_R13n_K17") (pintype "bidirectional"))
    )
    (net (code "156") (name "/SYS_DDS_SYNC_P") (class "Default")
      (node (ref "U8") (pin "K18") (pinfunction "IO,_DIFFIO_R13p,_(DQ0R)/(DQ1R)/(DQ1R)_K18") (pintype "bidirectional"))
    )
    (net (code "165") (name "/SYS_MOSI_0_N") (class "Default")
      (node (ref "R152") (pin "2") (pinfunction "2_2") (pintype "passive"))
    )
    (net (code "166") (name "/SYS_MOSI_0_P") (class "Default")
      (node (ref "R152") (pin "1") (pinfunction "1_1") (pintype "passive"))
    )
    (net (code "167") (name "/SYS_MOSI_1_N") (class "Default")
      (node (ref "R153") (pin "2") (pinfunction "2_2") (pintype "passive"))
    )
    (net (code "168") (name "/SYS_MOSI_1_P") (class "Default")
      (node (ref "R153") (pin "1") (pinfunction "1_1") (pintype "passive"))
    )
    (net (code "169") (name "/SYS_MOSI_2_N") (class "Default")
      (node (ref "R154") (pin "2") (pinfunction "2_2") (pintype "passive"))
    )
    (net (code "170") (name "/SYS_MOSI_2_P") (class "Default")
      (node (ref "R154") (pin "1") (pinfunction "1_1") (pintype "passive"))
    )
    (net (code "171") (name "/SYS_MOSI_3_N") (class "Default")
      (node (ref "R155") (pin "2") (pinfunction "2_2") (pintype "passive"))
    )
    (net (code "172") (name "/SYS_MOSI_3_P") (class "Default")
      (node (ref "R155") (pin "1") (pinfunction "1_1") (pintype "passive"))
    )
    (net (code "173") (name "/SYS_SCLK_N") (class "Default")
      (node (ref "R181") (pin "2") (pinfunction "2_2") (pintype "passive"))
      (node (ref "U8") (pin "G22") (pinfunction "CLK5,_DIFFCLK_2n_G22") (pintype "input"))
    )
    (net (code "174") (name "/SYS_SCLK_P") (class "Default")
      (node (ref "R181") (pin "1") (pinfunction "1_1") (pintype "passive"))
      (node (ref "U8") (pin "G21") (pinfunction "CLK4,_DIFFCLK_2p_G21") (pintype "input"))
    )
    (net (code "175") (name "/SYS_SPI_FMC.SYS_MISO_N_0") (class "Default")
      (node (ref "U8") (pin "H20") (pinfunction "IO,_DIFFIO_R9n,_(DQ0R)/(DQ1R)/(DQ1R)_H20") (pintype "bidirectional"))
    )
    (net (code "176") (name "/SYS_SPI_FMC.SYS_MISO_N_1") (class "Default")
      (node (ref "U8") (pin "G18") (pinfunction "IO,_DIFFIO_R5n,_(PADD23),_(DQ2R)/(DQ1R)/(DQ1R)_G18") (pintype "bidirectional"))
    )
    (net (code "177") (name "/SYS_SPI_FMC.SYS_MISO_N_2") (class "Default")
      (node (ref "U8") (pin "F20") (pinfunction "IO,_DIFFIO_R6n,_(nAVD),_(DQ2R)/(DQ1R)/(DQ1R)_F20") (pintype "bidirectional"))
    )
    (net (code "178") (name "/SYS_SPI_FMC.SYS_MISO_N_3") (class "Default")
      (node (ref "U8") (pin "F17") (pinfunction "IO,_DIFFIO_R1n,_(DQ2R)/(DQ1R)/(DQ1R)_F17") (pintype "bidirectional"))
    )
    (net (code "179") (name "/SYS_SPI_FMC.SYS_MISO_P_0") (class "Default")
      (node (ref "U8") (pin "H19") (pinfunction "IO,_DIFFIO_R9p,_(DQ0R)/(DQ1R)/(DQ1R)_H19") (pintype "bidirectional"))
    )
    (net (code "180") (name "/SYS_SPI_FMC.SYS_MISO_P_1") (class "Default")
      (node (ref "U8") (pin "H17") (pinfunction "IO,_DIFFIO_R5p_H17") (pintype "bidirectional"))
    )
    (net (code "181") (name "/SYS_SPI_FMC.SYS_MISO_P_2") (class "Default")
      (node (ref "U8") (pin "F19") (pinfunction "IO,_DIFFIO_R6p,_(DQ2R)/(DQ1R)/(DQ1R)_F19") (pintype "bidirectional"))
    )
    (net (code "182") (name "/SYS_SPI_FMC.SYS_MISO_P_3") (class "Default")
      (node (ref "U8") (pin "G17") (pinfunction "IO,_DIFFIO_R1p_G17") (pintype "bidirectional"))
    )
    (net (code "183") (name "/SYS_SPI_FMC.SYS_MOSI_N_0") (class "Default")
      (node (ref "U8") (pin "E22") (pinfunction "IO,_DIFFIO_R8n,_(nWE),_(DQ0R)/(DQ1R)/(DQ1R)_E22") (pintype "bidirectional"))
    )
    (net (code "184") (name "/SYS_SPI_FMC.SYS_MOSI_N_1") (class "Default")
      (node (ref "U8") (pin "D22") (pinfunction "IO,_DIFFIO_R7n,_(DM2R)/(DM1R/BWS#1R)/(DM1R/BWS#1R)_D22") (pintype "bidirectional"))
    )
    (net (code "185") (name "/SYS_SPI_FMC.SYS_MOSI_N_2") (class "Default")
      (node (ref "U8") (pin "C22") (pinfunction "IO,_DIFFIO_R4n,_(DQ2R)/(DQ1R)/(DQ1R)_C22") (pintype "bidirectional"))
    )
    (net (code "186") (name "/SYS_SPI_FMC.SYS_MOSI_N_3") (class "Default")
      (node (ref "U8") (pin "B22") (pinfunction "IO,_DIFFIO_R3n,_(PADD22),_(DQ2R)/(DQ1R)/(DQ1R)_B22") (pintype "bidirectional"))
    )
    (net (code "187") (name "/SYS_SPI_FMC.SYS_MOSI_P_0") (class "Default")
      (node (ref "U8") (pin "E21") (pinfunction "IO,_DIFFIO_R8p,_(nOE),__/(DQ1R)/(DQ1R)_E21") (pintype "bidirectional"))
    )
    (net (code "188") (name "/SYS_SPI_FMC.SYS_MOSI_P_1") (class "Default")
      (node (ref "U8") (pin "D21") (pinfunction "IO,_DIFFIO_R7p,__/(DQ1R)/(DQ1R)_D21") (pintype "bidirectional"))
    )
    (net (code "189") (name "/SYS_SPI_FMC.SYS_MOSI_P_2") (class "Default")
      (node (ref "U8") (pin "C21") (pinfunction "IO,_DIFFIO_R4p,_(DQ2R)/(DQ1R)/(DQ1R)_C21") (pintype "bidirectional"))
    )
    (net (code "190") (name "/SYS_SPI_FMC.SYS_MOSI_P_3") (class "Default")
      (node (ref "U8") (pin "B21") (pinfunction "IO,_DIFFIO_R3p,_(PADD21),_(DQ2R)/(DQ1R)/(DQ1R)_B21") (pintype "bidirectional"))
    )
    (net (code "192") (name "/SYS_~{CS}_N") (class "Default")
      (node (ref "U8") (pin "F22") (pinfunction "IO,_DIFFIO_R11n,_(DQ0R)/(DQ1R)/(DQ1R)_F22") (pintype "bidirectional"))
    )
    (net (code "193") (name "/SYS_~{CS}_P") (class "Default")
      (node (ref "U8") (pin "F21") (pinfunction "IO,_DIFFIO_R11p,_(DQ0R)/(DQ1R)/(DQ1R)_F21") (pintype "bidirectional"))
    )
    (net (code "194") (name "/TCK") (class "Default")
      (node (ref "U8") (pin "L2") (pinfunction "TCK_L2") (pintype "input"))
    )
    (net (code "195") (name "/TDI") (class "Default")
      (node (ref "U8") (pin "L5") (pinfunction "TDI_L5") (pintype "input"))
    )
    (net (code "196") (name "/TDO") (class "Default")
      (node (ref "U8") (pin "L4") (pinfunction "TDO_L4") (pintype "output"))
    )
    (net (code "197") (name "/TMS") (class "Default")
      (node (ref "U8") (pin "L1") (pinfunction "TMS_L1") (pintype "input"))
    )
    (net (code "198") (name "/fmc_io_in0") (class "Default")
      (node (ref "R160") (pin "8") (pinfunction "8_8") (pintype "passive"))
    )
    (net (code "199") (name "/fmc_io_in1") (class "Default")
      (node (ref "R160") (pin "7") (pinfunction "7_7") (pintype "passive"))
    )
    (net (code "200") (name "/fmc_io_in2") (class "Default")
      (node (ref "R160") (pin "6") (pinfunction "6_6") (pintype "passive"))
    )
    (net (code "201") (name "/fmc_io_in3") (class "Default")
      (node (ref "R160") (pin "5") (pinfunction "5_5") (pintype "passive"))
    )
    (net (code "202") (name "/fmc_io_in4") (class "Default")
      (node (ref "R162") (pin "8") (pinfunction "8_8") (pintype "passive"))
    )
    (net (code "203") (name "/fmc_io_in5") (class "Default")
      (node (ref "R162") (pin "7") (pinfunction "7_7") (pintype "passive"))
    )
    (net (code "204") (name "/fmc_io_in6") (class "Default")
      (node (ref "R162") (pin "6") (pinfunction "6_6") (pintype "passive"))
    )
    (net (code "205") (name "/fmc_io_in7") (class "Default")
      (node (ref "R162") (pin "5") (pinfunction "5_5") (pintype "passive"))
    )
    (net (code "207") (name "/fmc_io_out0") (class "Default")
      (node (ref "R161") (pin "8") (pinfunction "8_8") (pintype "passive"))
    )
    (net (code "208") (name "/fmc_io_out1") (class "Default")
      (node (ref "R161") (pin "7") (pinfunction "7_7") (pintype "passive"))
    )
    (net (code "209") (name "/fmc_io_out2") (class "Default")
      (node (ref "R161") (pin "6") (pinfunction "6_6") (pintype "passive"))
    )
    (net (code "210") (name "/fmc_io_out3") (class "Default")
      (node (ref "R161") (pin "5") (pinfunction "5_5") (pintype "passive"))
    )
    (net (code "211") (name "/fmc_io_out4") (class "Default")
      (node (ref "R163") (pin "8") (pinfunction "8_8") (pintype "passive"))
    )
    (net (code "212") (name "/fmc_io_out5") (class "Default")
      (node (ref "R163") (pin "7") (pinfunction "7_7") (pintype "passive"))
    )
    (net (code "213") (name "/fmc_io_out6") (class "Default")
      (node (ref "R163") (pin "6") (pinfunction "6_6") (pintype "passive"))
    )
    (net (code "214") (name "/fmc_io_out7") (class "Default")
      (node (ref "R163") (pin "5") (pinfunction "5_5") (pintype "passive"))
    )
    (net (code "216") (name "/io_in0") (class "Default")
      (node (ref "U8") (pin "Y14") (pinfunction "IO,_DIFFIO_B29p_Y14") (pintype "bidirectional"))
    )
    (net (code "217") (name "/io_in1") (class "Default")
      (node (ref "U8") (pin "AA13") (pinfunction "IO,_DIFFIO_B23p,_(DQ4B)/(DQ5B)/(DQ5B)_AA13") (pintype "bidirectional"))
    )
    (net (code "218") (name "/io_in2") (class "Default")
      (node (ref "U8") (pin "W17") (pinfunction "IO,_DIFFIO_B38p,_(DQ2B)/(DQ5B)/(DQ5B)_W17") (pintype "bidirectional"))
    )
    (net (code "219") (name "/io_in3") (class "Default")
      (node (ref "U8") (pin "AA17") (pinfunction "IO,_DIFFIO_B37p_AA17") (pintype "bidirectional"))
    )
    (net (code "220") (name "/io_in4") (class "Default")
      (node (ref "U8") (pin "AB16") (pinfunction "IO,_DIFFIO_B30n,_(DQ2B)/(DQ5B)/(DQ5B)_AB16") (pintype "bidirectional"))
    )
    (net (code "221") (name "/io_in5") (class "Default")
      (node (ref "U8") (pin "W15") (pinfunction "IO,_DIFFIO_B35p,_(DQ2B)/(DQ5B)/(DQ5B)_W15") (pintype "bidirectional"))
    )
    (net (code "222") (name "/io_in6") (class "Default")
      (node (ref "U8") (pin "AA15") (pinfunction "IO,_DIFFIO_B27p,_(DQ4B)/(DQ5B)/(DQ5B)_AA15") (pintype "bidirectional"))
    )
    (net (code "223") (name "/io_in7") (class "Default")
      (node (ref "U8") (pin "AB14") (pinfunction "IO,_DIFFIO_B25n,_(DQ4B)/(DQ5B)/(DQ5B)_AB14") (pintype "bidirectional"))
    )
    (net (code "225") (name "/io_out0") (class "Default")
      (node (ref "U8") (pin "AB13") (pinfunction "IO,_DIFFIO_B23n,_(DQ4B)/(DQ5B)/(DQ5B)_AB13") (pintype "bidirectional"))
    )
    (net (code "226") (name "/io_out1") (class "Default")
      (node (ref "U8") (pin "Y13") (pinfunction "IO,_DIFFIO_B26n,_(DQS4B/CQ5B,DPCLK4)/(DQS4B/CQ5B,DPCLK4)/(DQS4B/CQ5B,DPCLK4)_Y13") (pintype "bidirectional"))
    )
    (net (code "227") (name "/io_out2") (class "Default")
      (node (ref "U8") (pin "AB17") (pinfunction "IO,_DIFFIO_B37n_AB17") (pintype "bidirectional"))
    )
    (net (code "228") (name "/io_out3") (class "Default")
      (node (ref "U8") (pin "Y17") (pinfunction "IO,_DIFFIO_B38n,_(DQS0B/CQ1B,CDPCLK3)/(DQS0B/CQ1B,CDPCLK3)/(DQS0B/CQ1B,CDPCLK3)_Y17") (pintype "bidirectional"))
    )
    (net (code "229") (name "/io_out4") (class "Default")
      (node (ref "U8") (pin "AA16") (pinfunction "IO,_DIFFIO_B30p,_(DM2B)/(DM5B/BWS#5B)/(DM5B/BWS#5B)_AA16") (pintype "bidirectional"))
    )
    (net (code "230") (name "/io_out5") (class "Default")
      (node (ref "U8") (pin "AB15") (pinfunction "IO,_DIFFIO_B27n,_(DQ4B)/(DQ5B)/(DQ5B)_AB15") (pintype "bidirectional"))
    )
    (net (code "231") (name "/io_out6") (class "Default")
      (node (ref "U8") (pin "Y15") (pinfunction "IO,_DIFFIO_B29n_Y15") (pintype "bidirectional"))
    )
    (net (code "232") (name "/io_out7") (class "Default")
      (node (ref "U8") (pin "AA14") (pinfunction "IO,_DIFFIO_B25p,_(DQ4B)/(DQ5B)/(DQ5B)_AA14") (pintype "bidirectional"))
    )
    (net (code "234") (name "/nCEO") (class "Default")
      (node (ref "U8") (pin "K22") (pinfunction "IO,_DIFFIO_R16n,_(nCEO)_K22") (pintype "bidirectional+no_connect"))
    )
    (net (code "235") (name "/nCONFIG") (class "Default")
      (node (ref "U8") (pin "K5") (pinfunction "nCONFIG_K5") (pintype "input"))
    )
    (net (code "236") (name "/nSTATUS") (class "Default")
      (node (ref "U8") (pin "K6") (pinfunction "nSTATUS_K6") (pintype "bidirectional"))
    )
    (net (code "246") (name "/~{CS}") (class "Default")
      (node (ref "U8") (pin "H1") (pinfunction "IO,_DIFFIO_L13n,_(DQ0L)/(DQ1L)/(DQ1L)_H1") (pintype "bidirectional"))
    )
    (net (code "247") (name "/~{RESET}") (class "Default")
      (node (ref "U8") (pin "D2") (pinfunction "IO,_DIFFIO_L5p,_(DQ2L)/(DQ1L)/(DQ1L)_D2") (pintype "bidirectional"))
    )
    (net (code "248") (name "GND") (class "Default")
      (node (ref "U8") (pin "AA12") (pinfunction "CLK13,_DIFFCLK_7p_AA12") (pintype "input"))
      (node (ref "U8") (pin "AB11") (pinfunction "CLK14,_DIFFCLK_6n_AB11") (pintype "input"))
      (node (ref "U8") (pin "AB12") (pinfunction "CLK12,_DIFFCLK_7n_AB12") (pintype "input"))
      (node (ref "U8") (pin "G1") (pinfunction "CLK1,_DIFFCLK_0n_G1") (pintype "input"))
      (node (ref "U8") (pin "K21") (pinfunction "IO,_DIFFIO_R16p,_(CLKUSR)_K21") (pintype "bidirectional"))
      (node (ref "U8") (pin "L3") (pinfunction "nCE_L3") (pintype "input"))
      (node (ref "U8") (pin "N21") (pinfunction "IO,_DIFFIO_R20p,_(DEV_CLRn)_N21") (pintype "bidirectional"))
      (node (ref "U8") (pin "N22") (pinfunction "IO,_DIFFIO_R20n,_(DEV_OE)_N22") (pintype "bidirectional"))
      (node (ref "U8") (pin "T1") (pinfunction "CLK3,_DIFFCLK_1n_T1") (pintype "input"))
      (node (ref "U8") (pin "T2") (pinfunction "CLK2,_DIFFCLK_1p_T2") (pintype "input"))
      (node (ref "U8") (pin "T21") (pinfunction "CLK6,_DIFFCLK_3p_T21") (pintype "input"))
      (node (ref "U8") (pin "T22") (pinfunction "CLK7,_DIFFCLK_3n_T22") (pintype "input"))
    )
    (net (code "249") (name "Net-(U8G-IO,_DIFFIO_T24n,_(PADD11),_(DQ4T){slash}(DQ5T){slash}(DQ5T))") (class "Default")
      (node (ref "R160") (pin "1") (pinfunction "1_1") (pintype "passive"))
      (node (ref "U8") (pin "A13") (pinfunction "IO,_DIFFIO_T24n,_(PADD11),_(DQ4T)/(DQ5T)/(DQ5T)_A13") (pintype "bidirectional"))
    )
    (net (code "250") (name "Net-(U8G-IO,_DIFFIO_T25n,_(PADD9),_(DQ4T){slash}(DQ5T){slash}(DQ5T))") (class "Default")
      (node (ref "R160") (pin "4") (pinfunction "4_4") (pintype "passive"))
      (node (ref "U8") (pin "A14") (pinfunction "IO,_DIFFIO_T25n,_(PADD9),_(DQ4T)/(DQ5T)/(DQ5T)_A14") (pintype "bidirectional"))
    )
    (net (code "251") (name "Net-(U8G-IO,_DIFFIO_T25p,_(PADD10),_(DQ4T){slash}(DQ5T){slash}(DQ5T))") (class "Default")
      (node (ref "R162") (pin "1") (pinfunction "1_1") (pintype "passive"))
      (node (ref "U8") (pin "B14") (pinfunction "IO,_DIFFIO_T25p,_(PADD10),_(DQ4T)/(DQ5T)/(DQ5T)_B14") (pintype "bidirectional"))
    )
    (net (code "252") (name "Net-(U8G-IO,_DIFFIO_T26n,_(PADD7))") (class "Default")
      (node (ref "R160") (pin "3") (pinfunction "3_3") (pintype "passive"))
      (node (ref "U8") (pin "C13") (pinfunction "IO,_DIFFIO_T26n,_(PADD7)_C13") (pintype "bidirectional"))
    )
    (net (code "253") (name "Net-(U8G-IO,_DIFFIO_T26p,_(PADD8),_(DQ4T){slash}(DQ5T){slash}(DQ5T))") (class "Default")
      (node (ref "R160") (pin "2") (pinfunction "2_2") (pintype "passive"))
      (node (ref "U8") (pin "D13") (pinfunction "IO,_DIFFIO_T26p,_(PADD8),_(DQ4T)/(DQ5T)/(DQ5T)_D13") (pintype "bidirectional"))
    )
    (net (code "254") (name "Net-(U8G-IO,_DIFFIO_T27n,_(PADD5),_(DQ4T){slash}(DQ5T){slash}(DQ5T))") (class "Default")
      (node (ref "R162") (pin "2") (pinfunction "2_2") (pintype "passive"))
      (node (ref "U8") (pin "A15") (pinfunction "IO,_DIFFIO_T27n,_(PADD5),_(DQ4T)/(DQ5T)/(DQ5T)_A15") (pintype "bidirectional"))
    )
    (net (code "255") (name "Net-(U8G-IO,_DIFFIO_T27p,_(PADD6),_(DQ4T){slash}(DQ5T){slash}(DQ5T))") (class "Default")
      (node (ref "R162") (pin "3") (pinfunction "3_3") (pintype "passive"))
      (node (ref "U8") (pin "B15") (pinfunction "IO,_DIFFIO_T27p,_(PADD6),_(DQ4T)/(DQ5T)/(DQ5T)_B15") (pintype "bidirectional"))
    )
    (net (code "256") (name "Net-(U8G-IO,_DIFFIO_T30n,_(DM2T){slash}(DM5T{slash}BWS#5T){slash}(DM5T{slash}BWS#5T))") (class "Default")
      (node (ref "R162") (pin "4") (pinfunction "4_4") (pintype "passive"))
      (node (ref "U8") (pin "A16") (pinfunction "IO,_DIFFIO_T30n,_(DM2T)/(DM5T/BWS#5T)/(DM5T/BWS#5T)_A16") (pintype "bidirectional"))
    )
    (net (code "257") (name "Net-(U8G-IO,_DIFFIO_T30p,_(DQ4T){slash}(DQ5T){slash}(DQ5T))") (class "Default")
      (node (ref "R161") (pin "1") (pinfunction "1_1") (pintype "passive"))
      (node (ref "U8") (pin "B16") (pinfunction "IO,_DIFFIO_T30p,_(DQ4T)/(DQ5T)/(DQ5T)_B16") (pintype "bidirectional"))
    )
    (net (code "258") (name "Net-(U8G-IO,_DIFFIO_T31n,_(PADD1),_(DQ2T){slash}(DQ5T){slash}(DQ5T))") (class "Default")
      (node (ref "R161") (pin "2") (pinfunction "2_2") (pintype "passive"))
      (node (ref "U8") (pin "A17") (pinfunction "IO,_DIFFIO_T31n,_(PADD1),_(DQ2T)/(DQ5T)/(DQ5T)_A17") (pintype "bidirectional"))
    )
    (net (code "259") (name "Net-(U8G-IO,_DIFFIO_T31p,_(PADD2),__{slash}(DQ5T){slash}(DQ5T))") (class "Default")
      (node (ref "R161") (pin "3") (pinfunction "3_3") (pintype "passive"))
      (node (ref "U8") (pin "B17") (pinfunction "IO,_DIFFIO_T31p,_(PADD2),__/(DQ5T)/(DQ5T)_B17") (pintype "bidirectional"))
    )
    (net (code "260") (name "Net-(U8G-IO,_DIFFIO_T34n,_(DQ2T){slash}(DQ5T){slash}(DQ5T))") (class "Default")
      (node (ref "R163") (pin "1") (pinfunction "1_1") (pintype "passive"))
      (node (ref "U8") (pin "A18") (pinfunction "IO,_DIFFIO_T34n,_(DQ2T)/(DQ5T)/(DQ5T)_A18") (pintype "bidirectional"))
    )
    (net (code "261") (name "Net-(U8G-IO,_DIFFIO_T34p,_(PADD0))") (class "Default")
      (node (ref "R163") (pin "2") (pinfunction "2_2") (pintype "passive"))
      (node (ref "U8") (pin "B18") (pinfunction "IO,_DIFFIO_T34p,_(PADD0)_B18") (pintype "bidirectional"))
    )
    (net (code "262") (name "Net-(U8G-IO,_DIFFIO_T35p,_(DQ2T){slash}(DQ5T){slash}(DQ5T))") (class "Default")
      (node (ref "R161") (pin "4") (pinfunction "4_4") (pintype "passive"))
      (node (ref "U8") (pin "C17") (pinfunction "IO,_DIFFIO_T35p,_(DQ2T)/(DQ5T)/(DQ5T)_C17") (pintype "bidirectional"))
    )
    (net (code "263") (name "Net-(U8G-IO,_DIFFIO_T39n)") (class "Default")
      (node (ref "R163") (pin "3") (pinfunction "3_3") (pintype "passive"))
      (node (ref "U8") (pin "C18") (pinfunction "IO,_DIFFIO_T39n_C18") (pintype "bidirectional"))
    )
    (net (code "264") (name "Net-(U8G-IO,_DIFFIO_T39p)") (class "Default")
      (node (ref "R163") (pin "4") (pinfunction "4_4") (pintype "passive"))
      (node (ref "U8") (pin "D18") (pinfunction "IO,_DIFFIO_T39p_D18") (pintype "bidirectional"))
    )
    (net (code "265") (name "Net-(U8H-IO,_DIFFIO_T3n,_(DQ3T){slash}(DQ3T){slash}(DQ5T))") (class "Default")
      (node (ref "R178") (pin "7") (pinfunction "7_7") (pintype "passive"))
      (node (ref "U8") (pin "C3") (pinfunction "IO,_DIFFIO_T3n,_(DQ3T)/(DQ3T)/(DQ5T)_C3") (pintype "bidirectional"))
    )
    (net (code "266") (name "Net-(U8H-IO,_DIFFIO_T3p,_(DATA12),_(DQS1T{slash}CQ1T#,CDPCLK7){slash}(DQS1T{slash}CQ1T#,CDPCLK7){slash}(DQS1T{slash}CQ1T#,CDPCLK7))") (class "Default")
      (node (ref "R178") (pin "8") (pinfunction "8_8") (pintype "passive"))
      (node (ref "U8") (pin "C4") (pinfunction "IO,_DIFFIO_T3p,_(DATA12),_(DQS1T/CQ1T#,CDPCLK7)/(DQS1T/CQ1T#,CDPCLK7)/(DQS1T/CQ1T#,CDPCLK7)_C4") (pintype "bidirectional"))
    )
    (net (code "267") (name "Net-(U8H-IO,_DIFFIO_T5n,_(DATA10),_(DQ3T){slash}(DQ3T){slash}(DQ5T))") (class "Default")
      (node (ref "R178") (pin "5") (pinfunction "5_5") (pintype "passive"))
      (node (ref "U8") (pin "A3") (pinfunction "IO,_DIFFIO_T5n,_(DATA10),_(DQ3T)/(DQ3T)/(DQ5T)_A3") (pintype "bidirectional"))
    )
    (net (code "268") (name "Net-(U8H-IO,_DIFFIO_T5p,_(DATA11),_(DQ3T){slash}(DQ3T){slash}(DQ5T))") (class "Default")
      (node (ref "R178") (pin "6") (pinfunction "6_6") (pintype "passive"))
      (node (ref "U8") (pin "B3") (pinfunction "IO,_DIFFIO_T5p,_(DATA11),_(DQ3T)/(DQ3T)/(DQ5T)_B3") (pintype "bidirectional"))
    )
    (net (code "269") (name "unconnected-(U8A-IO,_DIFFIO_L11n-PadK7)") (class "Default")
      (node (ref "U8") (pin "K7") (pinfunction "IO,_DIFFIO_L11n_K7") (pintype "bidirectional"))
    )
    (net (code "270") (name "unconnected-(U8A-IO,_DIFFIO_L11p-PadJ7)") (class "Default")
      (node (ref "U8") (pin "J7") (pinfunction "IO,_DIFFIO_L11p_J7") (pintype "bidirectional"))
    )
    (net (code "271") (name "unconnected-(U8A-IO,_VREFB1N0-PadG5)") (class "Default")
      (node (ref "U8") (pin "G5") (pinfunction "IO,_VREFB1N0_G5") (pintype "bidirectional"))
    )
    (net (code "272") (name "unconnected-(U8A-IO,_VREFB1N1-PadH5)") (class "Default")
      (node (ref "U8") (pin "H5") (pinfunction "IO,_VREFB1N1_H5") (pintype "bidirectional"))
    )
    (net (code "273") (name "unconnected-(U8A-IO-PadH7)") (class "Default")
      (node (ref "U8") (pin "H7") (pinfunction "IO_H7") (pintype "bidirectional"))
    )
    (net (code "274") (name "unconnected-(U8A-IO-PadJ5)") (class "Default")
      (node (ref "U8") (pin "J5") (pinfunction "IO_J5") (pintype "bidirectional"))
    )
    (net (code "275") (name "unconnected-(U8B-IO,_(DQS3L{slash}CQ3L#,CDPCLK1){slash}(DQS3L{slash}CQ3L#,CDPCLK1){slash}(DQS3L{slash}CQ3L#,CDPCLK1)-PadT4)") (class "Default")
      (node (ref "U8") (pin "T4") (pinfunction "IO,_(DQS3L/CQ3L#,CDPCLK1)/(DQS3L/CQ3L#,CDPCLK1)/(DQS3L/CQ3L#,CDPCLK1)_T4") (pintype "bidirectional"))
    )
    (net (code "276") (name "unconnected-(U8B-IO,_DIFFIO_L27p-PadR4)") (class "Default")
      (node (ref "U8") (pin "R4") (pinfunction "IO,_DIFFIO_L27p_R4") (pintype "bidirectional"))
    )
    (net (code "277") (name "unconnected-(U8B-IO,_DIFFIO_L31n,_(DQ3L){slash}(DQ3L){slash}(DQ1L)-PadAA1)") (class "Default")
      (node (ref "U8") (pin "AA1") (pinfunction "IO,_DIFFIO_L31n,_(DQ3L)/(DQ3L)/(DQ1L)_AA1") (pintype "bidirectional"))
    )
    (net (code "278") (name "unconnected-(U8B-IO,_RDN1-PadV3)") (class "Default")
      (node (ref "U8") (pin "V3") (pinfunction "IO,_RDN1_V3") (pintype "bidirectional"))
    )
    (net (code "279") (name "unconnected-(U8B-IO,_RUP1-PadV4)") (class "Default")
      (node (ref "U8") (pin "V4") (pinfunction "IO,_RUP1_V4") (pintype "bidirectional"))
    )
    (net (code "280") (name "unconnected-(U8B-IO,_VREFB2N0-PadM5)") (class "Default")
      (node (ref "U8") (pin "M5") (pinfunction "IO,_VREFB2N0_M5") (pintype "bidirectional"))
    )
    (net (code "281") (name "unconnected-(U8B-IO,_VREFB2N1-PadT3)") (class "Default")
      (node (ref "U8") (pin "T3") (pinfunction "IO,_VREFB2N1_T3") (pintype "bidirectional"))
    )
    (net (code "282") (name "unconnected-(U8C-IO,_(DQS1B{slash}CQ1B#,CDPCLK2){slash}(DQS1B{slash}CQ1B#,CDPCLK2){slash}(DQS1B{slash}CQ1B#,CDPCLK2)-PadY6)") (class "Default")
      (node (ref "U8") (pin "Y6") (pinfunction "IO,_(DQS1B/CQ1B#,CDPCLK2)/(DQS1B/CQ1B#,CDPCLK2)/(DQS1B/CQ1B#,CDPCLK2)_Y6") (pintype "bidirectional"))
    )
    (net (code "283") (name "unconnected-(U8C-IO,_DIFFIO_B8p,_(DQ3B){slash}(DQ3B){slash}(DQ5B)-PadU9)") (class "Default")
      (node (ref "U8") (pin "U9") (pinfunction "IO,_DIFFIO_B8p,_(DQ3B)/(DQ3B)/(DQ5B)_U9") (pintype "bidirectional"))
    )
    (net (code "284") (name "unconnected-(U8C-IO,_DIFFIO_B13p-PadT10)") (class "Default")
      (node (ref "U8") (pin "T10") (pinfunction "IO,_DIFFIO_B13p_T10") (pintype "bidirectional"))
    )
    (net (code "285") (name "unconnected-(U8C-IO,_DIFFIO_B15p,_(DQS3B{slash}CQ3B#,DPCLK2){slash}(DQS3B{slash}CQ3B#,DPCLK2){slash}(DQS3B{slash}CQ3B#,DPCLK2)-PadV10)") (class "Default")
      (node (ref "U8") (pin "V10") (pinfunction "IO,_DIFFIO_B15p,_(DQS3B/CQ3B#,DPCLK2)/(DQS3B/CQ3B#,DPCLK2)/(DQS3B/CQ3B#,DPCLK2)_V10") (pintype "bidirectional"))
    )
    (net (code "286") (name "unconnected-(U8C-IO,_DIFFIO_B16n,_(DQ5B){slash}(DQ3B){slash}(DQ5B)-PadU10)") (class "Default")
      (node (ref "U8") (pin "U10") (pinfunction "IO,_DIFFIO_B16n,_(DQ5B)/(DQ3B)/(DQ5B)_U10") (pintype "bidirectional"))
    )
    (net (code "287") (name "unconnected-(U8C-IO,_PLL1_CLKOUTn-PadAB3)") (class "Default")
      (node (ref "U8") (pin "AB3") (pinfunction "IO,_PLL1_CLKOUTn_AB3") (pintype "bidirectional"))
    )
    (net (code "288") (name "unconnected-(U8C-IO,_PLL1_CLKOUTp-PadAA3)") (class "Default")
      (node (ref "U8") (pin "AA3") (pinfunction "IO,_PLL1_CLKOUTp_AA3") (pintype "bidirectional"))
    )
    (net (code "289") (name "unconnected-(U8C-IO,_VREFB3N0-PadV9)") (class "Default")
      (node (ref "U8") (pin "V9") (pinfunction "IO,_VREFB3N0_V9") (pintype "bidirectional"))
    )
    (net (code "290") (name "unconnected-(U8D-IO,_DIFFIO_B26p,_(DQ4B){slash}(DQ5B){slash}(DQ5B)-PadW13)") (class "Default")
      (node (ref "U8") (pin "W13") (pinfunction "IO,_DIFFIO_B26p,_(DQ4B)/(DQ5B)/(DQ5B)_W13") (pintype "bidirectional"))
    )
    (net (code "291") (name "unconnected-(U8D-IO,_DIFFIO_B28p,_(DQ4B){slash}(DQ5B){slash}(DQ5B)-PadU12)") (class "Default")
      (node (ref "U8") (pin "U12") (pinfunction "IO,_DIFFIO_B28p,_(DQ4B)/(DQ5B)/(DQ5B)_U12") (pintype "bidirectional"))
    )
    (net (code "292") (name "unconnected-(U8D-IO,_DIFFIO_B31p,_(DQS2B{slash}CQ3B,DPCLK5){slash}(DQS2B{slash}CQ3B,DPCLK5){slash}(DQS2B{slash}CQ3B,DPCLK5)-PadV13)") (class "Default")
      (node (ref "U8") (pin "V13") (pinfunction "IO,_DIFFIO_B31p,_(DQS2B/CQ3B,DPCLK5)/(DQS2B/CQ3B,DPCLK5)/(DQS2B/CQ3B,DPCLK5)_V13") (pintype "bidirectional"))
    )
    (net (code "293") (name "unconnected-(U8D-IO,_DIFFIO_B32p-PadU13)") (class "Default")
      (node (ref "U8") (pin "U13") (pinfunction "IO,_DIFFIO_B32p_U13") (pintype "bidirectional"))
    )
    (net (code "294") (name "unconnected-(U8D-IO,_DIFFIO_B33n-PadU14)") (class "Default")
      (node (ref "U8") (pin "U14") (pinfunction "IO,_DIFFIO_B33n_U14") (pintype "bidirectional"))
    )
    (net (code "295") (name "unconnected-(U8D-IO,_DIFFIO_B34p-PadU15)") (class "Default")
      (node (ref "U8") (pin "U15") (pinfunction "IO,_DIFFIO_B34p_U15") (pintype "bidirectional"))
    )
    (net (code "296") (name "unconnected-(U8D-IO,_DIFFIO_B36n,_(DQ2B){slash}(DQ5B){slash}(DQ5B)-PadT15)") (class "Default")
      (node (ref "U8") (pin "T15") (pinfunction "IO,_DIFFIO_B36n,_(DQ2B)/(DQ5B)/(DQ5B)_T15") (pintype "bidirectional"))
    )
    (net (code "297") (name "unconnected-(U8D-IO,_DIFFIO_B36p-PadT14)") (class "Default")
      (node (ref "U8") (pin "T14") (pinfunction "IO,_DIFFIO_B36p_T14") (pintype "bidirectional"))
    )
    (net (code "298") (name "unconnected-(U8D-IO,_DIFFIO_B40n-PadU17)") (class "Default")
      (node (ref "U8") (pin "U17") (pinfunction "IO,_DIFFIO_B40n_U17") (pintype "bidirectional"))
    )
    (net (code "299") (name "unconnected-(U8D-IO,_DIFFIO_B40p-PadU16)") (class "Default")
      (node (ref "U8") (pin "U16") (pinfunction "IO,_DIFFIO_B40p_U16") (pintype "bidirectional"))
    )
    (net (code "300") (name "unconnected-(U8D-IO,_DIFFIO_B41n-PadR15)") (class "Default")
      (node (ref "U8") (pin "R15") (pinfunction "IO,_DIFFIO_B41n_R15") (pintype "bidirectional"))
    )
    (net (code "301") (name "unconnected-(U8D-IO,_DIFFIO_B41p-PadR14)") (class "Default")
      (node (ref "U8") (pin "R14") (pinfunction "IO,_DIFFIO_B41p_R14") (pintype "bidirectional"))
    )
    (net (code "302") (name "unconnected-(U8D-IO,_PLL4_CLKOUTn-PadR16)") (class "Default")
      (node (ref "U8") (pin "R16") (pinfunction "IO,_PLL4_CLKOUTn_R16") (pintype "bidirectional"))
    )
    (net (code "303") (name "unconnected-(U8D-IO,_PLL4_CLKOUTp-PadT16)") (class "Default")
      (node (ref "U8") (pin "T16") (pinfunction "IO,_PLL4_CLKOUTp_T16") (pintype "bidirectional"))
    )
    (net (code "304") (name "unconnected-(U8D-IO,_RDN2-PadAB19)") (class "Default")
      (node (ref "U8") (pin "AB19") (pinfunction "IO,_RDN2_AB19") (pintype "bidirectional"))
    )
    (net (code "305") (name "unconnected-(U8D-IO,_RUP2-PadAA19)") (class "Default")
      (node (ref "U8") (pin "AA19") (pinfunction "IO,_RUP2_AA19") (pintype "bidirectional"))
    )
    (net (code "306") (name "unconnected-(U8D-IO,_VREFB4N1-PadV12)") (class "Default")
      (node (ref "U8") (pin "V12") (pinfunction "IO,_VREFB4N1_V12") (pintype "bidirectional"))
    )
    (net (code "307") (name "unconnected-(U8E-IO,_(DQS3R{slash}CQ3R#,CDPCLK4){slash}(DQS3R{slash}CQ3R#,CDPCLK4){slash}(DQS3R{slash}CQ3R#,CDPCLK4)-PadW20)") (class "Default")
      (node (ref "U8") (pin "W20") (pinfunction "IO,_(DQS3R/CQ3R#,CDPCLK4)/(DQS3R/CQ3R#,CDPCLK4)/(DQS3R/CQ3R#,CDPCLK4)_W20") (pintype "bidirectional"))
    )
    (net (code "308") (name "unconnected-(U8E-IO,_DIFFIO_R18n,_(DQ1R){slash}(DQ3R){slash}(DQ1R)-PadM20)") (class "Default")
      (node (ref "U8") (pin "M20") (pinfunction "IO,_DIFFIO_R18n,_(DQ1R)/(DQ3R)/(DQ1R)_M20") (pintype "bidirectional"))
    )
    (net (code "309") (name "unconnected-(U8E-IO,_DIFFIO_R18p,_(DQ1R){slash}(DQ3R){slash}(DQ1R)-PadM19)") (class "Default")
      (node (ref "U8") (pin "M19") (pinfunction "IO,_DIFFIO_R18p,_(DQ1R)/(DQ3R)/(DQ1R)_M19") (pintype "bidirectional"))
    )
    (net (code "310") (name "unconnected-(U8E-IO,_DIFFIO_R19n,_(DQ1R){slash}(DQ3R){slash}(DQ1R)-PadM22)") (class "Default")
      (node (ref "U8") (pin "M22") (pinfunction "IO,_DIFFIO_R19n,_(DQ1R)/(DQ3R)/(DQ1R)_M22") (pintype "bidirectional"))
    )
    (net (code "311") (name "unconnected-(U8E-IO,_DIFFIO_R19p,_(DQ1R){slash}(DQ3R){slash}(DQ1R)-PadM21)") (class "Default")
      (node (ref "U8") (pin "M21") (pinfunction "IO,_DIFFIO_R19p,_(DQ1R)/(DQ3R)/(DQ1R)_M21") (pintype "bidirectional"))
    )
    (net (code "312") (name "unconnected-(U8E-IO,_DIFFIO_R21n-PadN17)") (class "Default")
      (node (ref "U8") (pin "N17") (pinfunction "IO,_DIFFIO_R21n_N17") (pintype "bidirectional"))
    )
    (net (code "313") (name "unconnected-(U8E-IO,_DIFFIO_R21p,_(DQS1R{slash}CQ1R#,DPCLK6){slash}(DQS1R{slash}CQ1R#,DPCLK6){slash}(DQS1R{slash}CQ1R#,DPCLK6)-PadN18)") (class "Default")
      (node (ref "U8") (pin "N18") (pinfunction "IO,_DIFFIO_R21p,_(DQS1R/CQ1R#,DPCLK6)/(DQS1R/CQ1R#,DPCLK6)/(DQS1R/CQ1R#,DPCLK6)_N18") (pintype "bidirectional"))
    )
    (net (code "314") (name "unconnected-(U8E-IO,_DIFFIO_R22n,_(DQ1R){slash}(DQ3R){slash}(DQ1R)-PadN20)") (class "Default")
      (node (ref "U8") (pin "N20") (pinfunction "IO,_DIFFIO_R22n,_(DQ1R)/(DQ3R)/(DQ1R)_N20") (pintype "bidirectional"))
    )
    (net (code "315") (name "unconnected-(U8E-IO,_DIFFIO_R22p-PadN19)") (class "Default")
      (node (ref "U8") (pin "N19") (pinfunction "IO,_DIFFIO_R22p_N19") (pintype "bidirectional"))
    )
    (net (code "316") (name "unconnected-(U8E-IO,_DIFFIO_R23n,_(DQ1R){slash}(DQ3R){slash}(DQ1R)-PadP22)") (class "Default")
      (node (ref "U8") (pin "P22") (pinfunction "IO,_DIFFIO_R23n,_(DQ1R)/(DQ3R)/(DQ1R)_P22") (pintype "bidirectional"))
    )
    (net (code "317") (name "unconnected-(U8E-IO,_DIFFIO_R23p,_(DQ1R){slash}(DQ3R){slash}(DQ1R)-PadP21)") (class "Default")
      (node (ref "U8") (pin "P21") (pinfunction "IO,_DIFFIO_R23p,_(DQ1R)/(DQ3R)/(DQ1R)_P21") (pintype "bidirectional"))
    )
    (net (code "318") (name "unconnected-(U8E-IO,_DIFFIO_R24n,_(DQ1R){slash}(DQ3R){slash}(DQ1R)-PadR22)") (class "Default")
      (node (ref "U8") (pin "R22") (pinfunction "IO,_DIFFIO_R24n,_(DQ1R)/(DQ3R)/(DQ1R)_R22") (pintype "bidirectional"))
    )
    (net (code "319") (name "unconnected-(U8E-IO,_DIFFIO_R24p,_(DQ1R){slash}(DQ3R){slash}(DQ1R)-PadR21)") (class "Default")
      (node (ref "U8") (pin "R21") (pinfunction "IO,_DIFFIO_R24p,_(DQ1R)/(DQ3R)/(DQ1R)_R21") (pintype "bidirectional"))
    )
    (net (code "320") (name "unconnected-(U8E-IO,_DIFFIO_R25p-PadN16)") (class "Default")
      (node (ref "U8") (pin "N16") (pinfunction "IO,_DIFFIO_R25p_N16") (pintype "bidirectional"))
    )
    (net (code "321") (name "unconnected-(U8E-IO,_DIFFIO_R26n-PadR18)") (class "Default")
      (node (ref "U8") (pin "R18") (pinfunction "IO,_DIFFIO_R26n_R18") (pintype "bidirectional"))
    )
    (net (code "322") (name "unconnected-(U8E-IO,_DIFFIO_R26p,_(DM1R{slash}BWS#1R){slash}(DM3R{slash}BWS#3R){slash}(DM1R{slash}BWS#1R)-PadR19)") (class "Default")
      (node (ref "U8") (pin "R19") (pinfunction "IO,_DIFFIO_R26p,_(DM1R/BWS#1R)/(DM3R/BWS#3R)/(DM1R/BWS#1R)_R19") (pintype "bidirectional"))
    )
    (net (code "323") (name "unconnected-(U8E-IO,_DIFFIO_R28n,_(DQ3R){slash}(DQ3R){slash}(DQ1R)-PadR20)") (class "Default")
      (node (ref "U8") (pin "R20") (pinfunction "IO,_DIFFIO_R28n,_(DQ3R)/(DQ3R)/(DQ1R)_R20") (pintype "bidirectional"))
    )
    (net (code "324") (name "unconnected-(U8E-IO,_DIFFIO_R30n-PadR17)") (class "Default")
      (node (ref "U8") (pin "R17") (pinfunction "IO,_DIFFIO_R30n_R17") (pintype "bidirectional"))
    )
    (net (code "325") (name "unconnected-(U8E-IO,_DIFFIO_R30p-PadP17)") (class "Default")
      (node (ref "U8") (pin "P17") (pinfunction "IO,_DIFFIO_R30p_P17") (pintype "bidirectional"))
    )
    (net (code "326") (name "unconnected-(U8E-IO,_DIFFIO_R31n-PadT20)") (class "Default")
      (node (ref "U8") (pin "T20") (pinfunction "IO,_DIFFIO_R31n_T20") (pintype "bidirectional"))
    )
    (net (code "327") (name "unconnected-(U8E-IO,_DIFFIO_R31p-PadT19)") (class "Default")
      (node (ref "U8") (pin "T19") (pinfunction "IO,_DIFFIO_R31p_T19") (pintype "bidirectional"))
    )
    (net (code "328") (name "unconnected-(U8E-IO,_DIFFIO_R34n,_(DQ3R){slash}(DQ3R){slash}(DQ1R)-PadU20)") (class "Default")
      (node (ref "U8") (pin "U20") (pinfunction "IO,_DIFFIO_R34n,_(DQ3R)/(DQ3R)/(DQ1R)_U20") (pintype "bidirectional"))
    )
    (net (code "329") (name "unconnected-(U8E-IO,_DIFFIO_R34p-PadU19)") (class "Default")
      (node (ref "U8") (pin "U19") (pinfunction "IO,_DIFFIO_R34p_U19") (pintype "bidirectional"))
    )
    (net (code "330") (name "unconnected-(U8E-IO,_DIFFIO_R36p,_(DM3R{slash}BWS#3R){slash}(DM3R{slash}BWS#3R){slash}(DM1R{slash}BWS#1R)-PadAA21)") (class "Default")
      (node (ref "U8") (pin "AA21") (pinfunction "IO,_DIFFIO_R36p,_(DM3R/BWS#3R)/(DM3R/BWS#3R)/(DM1R/BWS#1R)_AA21") (pintype "bidirectional"))
    )
    (net (code "331") (name "unconnected-(U8E-IO,_RDN3-PadT18)") (class "Default")
      (node (ref "U8") (pin "T18") (pinfunction "IO,_RDN3_T18") (pintype "bidirectional"))
    )
    (net (code "332") (name "unconnected-(U8E-IO,_RUP3-PadT17)") (class "Default")
      (node (ref "U8") (pin "T17") (pinfunction "IO,_RUP3_T17") (pintype "bidirectional"))
    )
    (net (code "333") (name "unconnected-(U8E-IO,_VREFB5N0-PadP20)") (class "Default")
      (node (ref "U8") (pin "P20") (pinfunction "IO,_VREFB5N0_P20") (pintype "bidirectional"))
    )
    (net (code "334") (name "unconnected-(U8E-IO,_VREFB5N1-PadW19)") (class "Default")
      (node (ref "U8") (pin "W19") (pinfunction "IO,_VREFB5N1_W19") (pintype "bidirectional"))
    )
    (net (code "335") (name "unconnected-(U8E-IO-PadM16)") (class "Default")
      (node (ref "U8") (pin "M16") (pinfunction "IO_M16") (pintype "bidirectional"))
    )
    (net (code "336") (name "unconnected-(U8F-IO,_DIFFIO_R2n,_(PADD20),_(DQS2R{slash}CQ3R,CDPCLK5){slash}(DQS2R{slash}CQ3R,CDPCLK5){slash}(DQS2R{slash}CQ3R,CDPCLK5)-PadC20)") (class "Default")
      (node (ref "U8") (pin "C20") (pinfunction "IO,_DIFFIO_R2n,_(PADD20),_(DQS2R/CQ3R,CDPCLK5)/(DQS2R/CQ3R,CDPCLK5)/(DQS2R/CQ3R,CDPCLK5)_C20") (pintype "bidirectional"))
    )
    (net (code "337") (name "unconnected-(U8F-IO,_DIFFIO_R2p-PadD20)") (class "Default")
      (node (ref "U8") (pin "D20") (pinfunction "IO,_DIFFIO_R2p_D20") (pintype "bidirectional"))
    )
    (net (code "338") (name "unconnected-(U8F-IO,_DIFFIO_R10n-PadJ20)") (class "Default")
      (node (ref "U8") (pin "J20") (pinfunction "IO,_DIFFIO_R10n_J20") (pintype "bidirectional"))
    )
    (net (code "339") (name "unconnected-(U8F-IO,_DIFFIO_R10p-PadJ19)") (class "Default")
      (node (ref "U8") (pin "J19") (pinfunction "IO,_DIFFIO_R10p_J19") (pintype "bidirectional"))
    )
    (net (code "340") (name "unconnected-(U8F-IO,_DIFFIO_R12n-PadJ18)") (class "Default")
      (node (ref "U8") (pin "J18") (pinfunction "IO,_DIFFIO_R12n_J18") (pintype "bidirectional"))
    )
    (net (code "341") (name "unconnected-(U8F-IO,_DIFFIO_R14n,_(DQ0R){slash}(DQ1R){slash}(DQ1R)-PadH22)") (class "Default")
      (node (ref "U8") (pin "H22") (pinfunction "IO,_DIFFIO_R14n,_(DQ0R)/(DQ1R)/(DQ1R)_H22") (pintype "bidirectional"))
    )
    (net (code "342") (name "unconnected-(U8F-IO,_DIFFIO_R14p,_(DQ0R){slash}(DQ1R){slash}(DQ1R)-PadH21)") (class "Default")
      (node (ref "U8") (pin "H21") (pinfunction "IO,_DIFFIO_R14p,_(DQ0R)/(DQ1R)/(DQ1R)_H21") (pintype "bidirectional"))
    )
    (net (code "343") (name "unconnected-(U8F-IO,_DIFFIO_R15n,_(DQS0R{slash}CQ1R,DPCLK7){slash}(DQS0R{slash}CQ1R,DPCLK7){slash}(DQS0R{slash}CQ1R,DPCLK7)-PadJ22)") (class "Default")
      (node (ref "U8") (pin "J22") (pinfunction "IO,_DIFFIO_R15n,_(DQS0R/CQ1R,DPCLK7)/(DQS0R/CQ1R,DPCLK7)/(DQS0R/CQ1R,DPCLK7)_J22") (pintype "bidirectional"))
    )
    (net (code "344") (name "unconnected-(U8F-IO,_DIFFIO_R15p,_(DM0R){slash}(DM1R{slash}BWS#1R){slash}(DM1R{slash}BWS#1R)-PadJ21)") (class "Default")
      (node (ref "U8") (pin "J21") (pinfunction "IO,_DIFFIO_R15p,_(DM0R)/(DM1R/BWS#1R)/(DM1R/BWS#1R)_J21") (pintype "bidirectional"))
    )
    (net (code "345") (name "unconnected-(U8F-IO,_VREFB6N0-PadH18)") (class "Default")
      (node (ref "U8") (pin "H18") (pinfunction "IO,_VREFB6N0_H18") (pintype "bidirectional"))
    )
    (net (code "346") (name "unconnected-(U8F-IO,_VREFB6N1-PadK19)") (class "Default")
      (node (ref "U8") (pin "K19") (pinfunction "IO,_VREFB6N1_K19") (pintype "bidirectional"))
    )
    (net (code "347") (name "unconnected-(U8F-IO-PadH16)") (class "Default")
      (node (ref "U8") (pin "H16") (pinfunction "IO_H16") (pintype "bidirectional"))
    )
    (net (code "348") (name "unconnected-(U8F-IO-PadJ17)") (class "Default")
      (node (ref "U8") (pin "J17") (pinfunction "IO_J17") (pintype "bidirectional"))
    )
    (net (code "349") (name "unconnected-(U8G-IO,_DIFFIO_T23n,_(PADD13)-PadE11)") (class "Default")
      (node (ref "U8") (pin "E11") (pinfunction "IO,_DIFFIO_T23n,_(PADD13)_E11") (pintype "bidirectional"))
    )
    (net (code "350") (name "unconnected-(U8G-IO,_DIFFIO_T23p,_(PADD14),_(DM4T){slash}(DM5T{slash}BWS#5T){slash}(DM5T{slash}BWS#5T)-PadF11)") (class "Default")
      (node (ref "U8") (pin "F11") (pinfunction "IO,_DIFFIO_T23p,_(PADD14),_(DM4T)/(DM5T/BWS#5T)/(DM5T/BWS#5T)_F11") (pintype "bidirectional"))
    )
    (net (code "351") (name "unconnected-(U8G-IO,_DIFFIO_T24p,_(PADD12),_(DQS4T{slash}CQ5T,DPCLK9){slash}(DQS4T{slash}CQ5T,DPCLK9){slash}(DQS4T{slash}CQ5T,DPCLK9)-PadB13)") (class "Default")
      (node (ref "U8") (pin "B13") (pinfunction "IO,_DIFFIO_T24p,_(PADD12),_(DQS4T/CQ5T,DPCLK9)/(DQS4T/CQ5T,DPCLK9)/(DQS4T/CQ5T,DPCLK9)_B13") (pintype "bidirectional"))
    )
    (net (code "352") (name "unconnected-(U8G-IO,_DIFFIO_T28n,_(PADD3),_(DQ4T){slash}(DQ5T){slash}(DQ5T)-PadE14)") (class "Default")
      (node (ref "U8") (pin "E14") (pinfunction "IO,_DIFFIO_T28n,_(PADD3),_(DQ4T)/(DQ5T)/(DQ5T)_E14") (pintype "bidirectional"))
    )
    (net (code "353") (name "unconnected-(U8G-IO,_DIFFIO_T28p,_(PADD4),_(DQS2T{slash}CQ3T,DPCLK8){slash}(DQS2T{slash}CQ3T,DPCLK8){slash}(DQS2T{slash}CQ3T,DPCLK8)-PadF13)") (class "Default")
      (node (ref "U8") (pin "F13") (pinfunction "IO,_DIFFIO_T28p,_(PADD4),_(DQS2T/CQ3T,DPCLK8)/(DQS2T/CQ3T,DPCLK8)/(DQS2T/CQ3T,DPCLK8)_F13") (pintype "bidirectional"))
    )
    (net (code "354") (name "unconnected-(U8G-IO,_DIFFIO_T32n-PadG14)") (class "Default")
      (node (ref "U8") (pin "G14") (pinfunction "IO,_DIFFIO_T32n_G14") (pintype "bidirectional"))
    )
    (net (code "355") (name "unconnected-(U8G-IO,_DIFFIO_T32p-PadG13)") (class "Default")
      (node (ref "U8") (pin "G13") (pinfunction "IO,_DIFFIO_T32p_G13") (pintype "bidirectional"))
    )
    (net (code "356") (name "unconnected-(U8G-IO,_DIFFIO_T33n-PadD15)") (class "Default")
      (node (ref "U8") (pin "D15") (pinfunction "IO,_DIFFIO_T33n_D15") (pintype "bidirectional"))
    )
    (net (code "357") (name "unconnected-(U8G-IO,_DIFFIO_T33p,_(DQ2T){slash}(DQ5T){slash}(DQ5T)-PadE15)") (class "Default")
      (node (ref "U8") (pin "E15") (pinfunction "IO,_DIFFIO_T33p,_(DQ2T)/(DQ5T)/(DQ5T)_E15") (pintype "bidirectional"))
    )
    (net (code "358") (name "unconnected-(U8G-IO,_DIFFIO_T37n,_(DQ2T){slash}(DQ5T){slash}(DQ5T)-PadC19)") (class "Default")
      (node (ref "U8") (pin "C19") (pinfunction "IO,_DIFFIO_T37n,_(DQ2T)/(DQ5T)/(DQ5T)_C19") (pintype "bidirectional"))
    )
    (net (code "359") (name "unconnected-(U8G-IO,_DIFFIO_T37p,_(DQ2T){slash}(DQ5T){slash}(DQ5T)-PadD19)") (class "Default")
      (node (ref "U8") (pin "D19") (pinfunction "IO,_DIFFIO_T37p,_(DQ2T)/(DQ5T)/(DQ5T)_D19") (pintype "bidirectional"))
    )
    (net (code "360") (name "unconnected-(U8G-IO,_DIFFIO_T40n-PadG15)") (class "Default")
      (node (ref "U8") (pin "G15") (pinfunction "IO,_DIFFIO_T40n_G15") (pintype "bidirectional"))
    )
    (net (code "361") (name "unconnected-(U8G-IO,_DIFFIO_T40p,_(DQS0T{slash}CQ1T,CDPCLK6){slash}(DQS0T{slash}CQ1T,CDPCLK6){slash}(DQS0T{slash}CQ1T,CDPCLK6)-PadF14)") (class "Default")
      (node (ref "U8") (pin "F14") (pinfunction "IO,_DIFFIO_T40p,_(DQS0T/CQ1T,CDPCLK6)/(DQS0T/CQ1T,CDPCLK6)/(DQS0T/CQ1T,CDPCLK6)_F14") (pintype "bidirectional"))
    )
    (net (code "362") (name "unconnected-(U8G-IO,_DIFFIO_T41n,_(DQ2T){slash}(DQ5T){slash}(DQ5T)-PadF15)") (class "Default")
      (node (ref "U8") (pin "F15") (pinfunction "IO,_DIFFIO_T41n,_(DQ2T)/(DQ5T)/(DQ5T)_F15") (pintype "bidirectional"))
    )
    (net (code "363") (name "unconnected-(U8G-IO,_DIFFIO_T41p-PadG16)") (class "Default")
      (node (ref "U8") (pin "G16") (pinfunction "IO,_DIFFIO_T41p_G16") (pintype "bidirectional"))
    )
    (net (code "364") (name "unconnected-(U8G-IO,_DIFFIO_T42n-PadF16)") (class "Default")
      (node (ref "U8") (pin "F16") (pinfunction "IO,_DIFFIO_T42n_F16") (pintype "bidirectional"))
    )
    (net (code "365") (name "unconnected-(U8G-IO,_DIFFIO_T42p,_(DQ2T){slash}(DQ5T){slash}(DQ5T)-PadE16)") (class "Default")
      (node (ref "U8") (pin "E16") (pinfunction "IO,_DIFFIO_T42p,_(DQ2T)/(DQ5T)/(DQ5T)_E16") (pintype "bidirectional"))
    )
    (net (code "366") (name "unconnected-(U8G-IO,_PLL2_CLKOUTn-PadA20)") (class "Default")
      (node (ref "U8") (pin "A20") (pinfunction "IO,_PLL2_CLKOUTn_A20") (pintype "bidirectional"))
    )
    (net (code "367") (name "unconnected-(U8G-IO,_PLL2_CLKOUTp-PadB20)") (class "Default")
      (node (ref "U8") (pin "B20") (pinfunction "IO,_PLL2_CLKOUTp_B20") (pintype "bidirectional"))
    )
    (net (code "368") (name "unconnected-(U8G-IO,_RDN4-PadA19)") (class "Default")
      (node (ref "U8") (pin "A19") (pinfunction "IO,_RDN4_A19") (pintype "bidirectional"))
    )
    (net (code "369") (name "unconnected-(U8G-IO,_RUP4-PadB19)") (class "Default")
      (node (ref "U8") (pin "B19") (pinfunction "IO,_RUP4_B19") (pintype "bidirectional"))
    )
    (net (code "370") (name "unconnected-(U8G-IO,_VREFB7N0-PadD17)") (class "Default")
      (node (ref "U8") (pin "D17") (pinfunction "IO,_VREFB7N0_D17") (pintype "bidirectional"))
    )
    (net (code "371") (name "unconnected-(U8G-IO,_VREFB7N1-PadC15)") (class "Default")
      (node (ref "U8") (pin "C15") (pinfunction "IO,_VREFB7N1_C15") (pintype "bidirectional"))
    )
    (net (code "372") (name "unconnected-(U8G-IO,__{slash}(DQ5T){slash}(DQ5T)-PadE12)") (class "Default")
      (node (ref "U8") (pin "E12") (pinfunction "IO,__/(DQ5T)/(DQ5T)_E12") (pintype "bidirectional"))
    )
    (net (code "373") (name "unconnected-(U8G-IO-PadE13)") (class "Default")
      (node (ref "U8") (pin "E13") (pinfunction "IO_E13") (pintype "bidirectional"))
    )
    (net (code "374") (name "unconnected-(U8H-IO,_DIFFIO_T1n-PadG9)") (class "Default")
      (node (ref "U8") (pin "G9") (pinfunction "IO,_DIFFIO_T1n_G9") (pintype "bidirectional"))
    )
    (net (code "375") (name "unconnected-(U8H-IO,_DIFFIO_T2n,_(DM3T{slash}BWS#3T){slash}(DM3T{slash}BWS#3T){slash}(DM5T{slash}BWS#5T)-PadF7)") (class "Default")
      (node (ref "U8") (pin "F7") (pinfunction "IO,_DIFFIO_T2n,_(DM3T/BWS#3T)/(DM3T/BWS#3T)/(DM5T/BWS#5T)_F7") (pintype "bidirectional"))
    )
    (net (code "376") (name "unconnected-(U8H-IO,_DIFFIO_T2p-PadG7)") (class "Default")
      (node (ref "U8") (pin "G7") (pinfunction "IO,_DIFFIO_T2p_G7") (pintype "bidirectional"))
    )
    (net (code "377") (name "unconnected-(U8H-IO,_DIFFIO_T4n-PadD6)") (class "Default")
      (node (ref "U8") (pin "D6") (pinfunction "IO,_DIFFIO_T4n_D6") (pintype "bidirectional"))
    )
    (net (code "378") (name "unconnected-(U8H-IO,_DIFFIO_T4p-PadE7)") (class "Default")
      (node (ref "U8") (pin "E7") (pinfunction "IO,_DIFFIO_T4p_E7") (pintype "bidirectional"))
    )
    (net (code "379") (name "unconnected-(U8H-IO,_DIFFIO_T7n,_(DATA9),_(DQ3T){slash}(DQ3T){slash}(DQ5T)-PadF8)") (class "Default")
      (node (ref "U8") (pin "F8") (pinfunction "IO,_DIFFIO_T7n,_(DATA9),_(DQ3T)/(DQ3T)/(DQ5T)_F8") (pintype "bidirectional"))
    )
    (net (code "380") (name "unconnected-(U8H-IO,_DIFFIO_T7p-PadG8)") (class "Default")
      (node (ref "U8") (pin "G8") (pinfunction "IO,_DIFFIO_T7p_G8") (pintype "bidirectional"))
    )
    (net (code "381") (name "unconnected-(U8H-IO,_DIFFIO_T9n,_(DATA7),_(DQ3T){slash}(DQ3T){slash}(DQ5T)-PadC6)") (class "Default")
      (node (ref "U8") (pin "C6") (pinfunction "IO,_DIFFIO_T9n,_(DATA7),_(DQ3T)/(DQ3T)/(DQ5T)_C6") (pintype "bidirectional"))
    )
    (net (code "382") (name "unconnected-(U8H-IO,_DIFFIO_T9p-PadD7)") (class "Default")
      (node (ref "U8") (pin "D7") (pinfunction "IO,_DIFFIO_T9p_D7") (pintype "bidirectional"))
    )
    (net (code "383") (name "unconnected-(U8H-IO,_DIFFIO_T10n-PadG10)") (class "Default")
      (node (ref "U8") (pin "G10") (pinfunction "IO,_DIFFIO_T10n_G10") (pintype "bidirectional"))
    )
    (net (code "384") (name "unconnected-(U8H-IO,_DIFFIO_T10p,_(DATA6),_(DQ3T){slash}(DQ3T){slash}(DQ5T)-PadF10)") (class "Default")
      (node (ref "U8") (pin "F10") (pinfunction "IO,_DIFFIO_T10p,_(DATA6),_(DQ3T)/(DQ3T)/(DQ5T)_F10") (pintype "bidirectional"))
    )
    (net (code "385") (name "unconnected-(U8H-IO,_DIFFIO_T12n-PadD8)") (class "Default")
      (node (ref "U8") (pin "D8") (pinfunction "IO,_DIFFIO_T12n_D8") (pintype "bidirectional"))
    )
    (net (code "386") (name "unconnected-(U8H-IO,_DIFFIO_T12p-PadE8)") (class "Default")
      (node (ref "U8") (pin "E8") (pinfunction "IO,_DIFFIO_T12p_E8") (pintype "bidirectional"))
    )
    (net (code "387") (name "unconnected-(U8H-IO,_DIFFIO_T13n,_(DATA14),_(DQS3T{slash}CQ3T#,DPCLK11){slash}(DQS3T{slash}CQ3T#,DPCLK11){slash}(DQS3T{slash}CQ3T#,DPCLK11)-PadC8)") (class "Default")
      (node (ref "U8") (pin "C8") (pinfunction "IO,_DIFFIO_T13n,_(DATA14),_(DQS3T/CQ3T#,DPCLK11)/(DQS3T/CQ3T#,DPCLK11)/(DQS3T/CQ3T#,DPCLK11)_C8") (pintype "bidirectional"))
    )
    (net (code "388") (name "unconnected-(U8H-IO,_DIFFIO_T13p,_(DATA13),_(DM5T{slash}BWS#5T){slash}(DM3T{slash}BWS#3T){slash}(DM5T{slash}BWS#5T)-PadC7)") (class "Default")
      (node (ref "U8") (pin "C7") (pinfunction "IO,_DIFFIO_T13p,_(DATA13),_(DM5T/BWS#5T)/(DM3T/BWS#3T)/(DM5T/BWS#5T)_C7") (pintype "bidirectional"))
    )
    (net (code "389") (name "unconnected-(U8H-IO,_DIFFIO_T14n-PadE9)") (class "Default")
      (node (ref "U8") (pin "E9") (pinfunction "IO,_DIFFIO_T14n_E9") (pintype "bidirectional"))
    )
    (net (code "390") (name "unconnected-(U8H-IO,_DIFFIO_T17p,_(DATA3),_(DQ5T){slash}(DQ3T){slash}(DQ5T)-PadB8)") (class "Default")
      (node (ref "U8") (pin "B8") (pinfunction "IO,_DIFFIO_T17p,_(DATA3),_(DQ5T)/(DQ3T)/(DQ5T)_B8") (pintype "bidirectional"))
    )
    (net (code "391") (name "unconnected-(U8H-IO,_DIFFIO_T18n-PadG11)") (class "Default")
      (node (ref "U8") (pin "G11") (pinfunction "IO,_DIFFIO_T18n_G11") (pintype "bidirectional"))
    )
    (net (code "392") (name "unconnected-(U8H-IO,_DIFFIO_T20n,_(PADD16),_(DQ5T){slash}(DQ3T){slash}(DQ5T)-PadA9)") (class "Default")
      (node (ref "U8") (pin "A9") (pinfunction "IO,_DIFFIO_T20n,_(PADD16),_(DQ5T)/(DQ3T)/(DQ5T)_A9") (pintype "bidirectional"))
    )
    (net (code "393") (name "unconnected-(U8H-IO,_DIFFIO_T20p,_(PADD17),_(DQS5T{slash}CQ5T#,DPCLK10){slash}(DQS5T{slash}CQ5T#,DPCLK10){slash}(DQS5T{slash}CQ5T#,DPCLK10)-PadB9)") (class "Default")
      (node (ref "U8") (pin "B9") (pinfunction "IO,_DIFFIO_T20p,_(PADD17),_(DQS5T/CQ5T#,DPCLK10)/(DQS5T/CQ5T#,DPCLK10)/(DQS5T/CQ5T#,DPCLK10)_B9") (pintype "bidirectional"))
    )
    (net (code "394") (name "unconnected-(U8H-IO,_DIFFIO_T21n,_(DQ5T){slash}(DQ3T){slash}(DQ5T)-PadA10)") (class "Default")
      (node (ref "U8") (pin "A10") (pinfunction "IO,_DIFFIO_T21n,_(DQ5T)/(DQ3T)/(DQ5T)_A10") (pintype "bidirectional"))
    )
    (net (code "395") (name "unconnected-(U8H-IO,_DIFFIO_T21p,_(PADD15)-PadB10)") (class "Default")
      (node (ref "U8") (pin "B10") (pinfunction "IO,_DIFFIO_T21p,_(PADD15)_B10") (pintype "bidirectional"))
    )
    (net (code "396") (name "unconnected-(U8H-IO,_DIFFIO_T22n,_(DQ5T){slash}(DQ3T){slash}(DQ5T)-PadD10)") (class "Default")
      (node (ref "U8") (pin "D10") (pinfunction "IO,_DIFFIO_T22n,_(DQ5T)/(DQ3T)/(DQ5T)_D10") (pintype "bidirectional"))
    )
    (net (code "397") (name "unconnected-(U8H-IO,_DIFFIO_T22p-PadE10)") (class "Default")
      (node (ref "U8") (pin "E10") (pinfunction "IO,_DIFFIO_T22p_E10") (pintype "bidirectional"))
    )
    (net (code "398") (name "unconnected-(U8H-IO,_VREFB8N0-PadC10)") (class "Default")
      (node (ref "U8") (pin "C10") (pinfunction "IO,_VREFB8N0_C10") (pintype "bidirectional"))
    )
    (net (code "399") (name "unconnected-(U8H-IO,_VREFB8N1-PadB5)") (class "Default")
      (node (ref "U8") (pin "B5") (pinfunction "IO,_VREFB8N1_B5") (pintype "bidirectional"))
    )
    (net (code "400") (name "unconnected-(U8H-IO-PadF9)") (class "Default")
      (node (ref "U8") (pin "F9") (pinfunction "IO_F9") (pintype "bidirectional"))
    )
  )
)
